# Connectors.net
KiCad netlist of a schematic drawn in Altium Designer
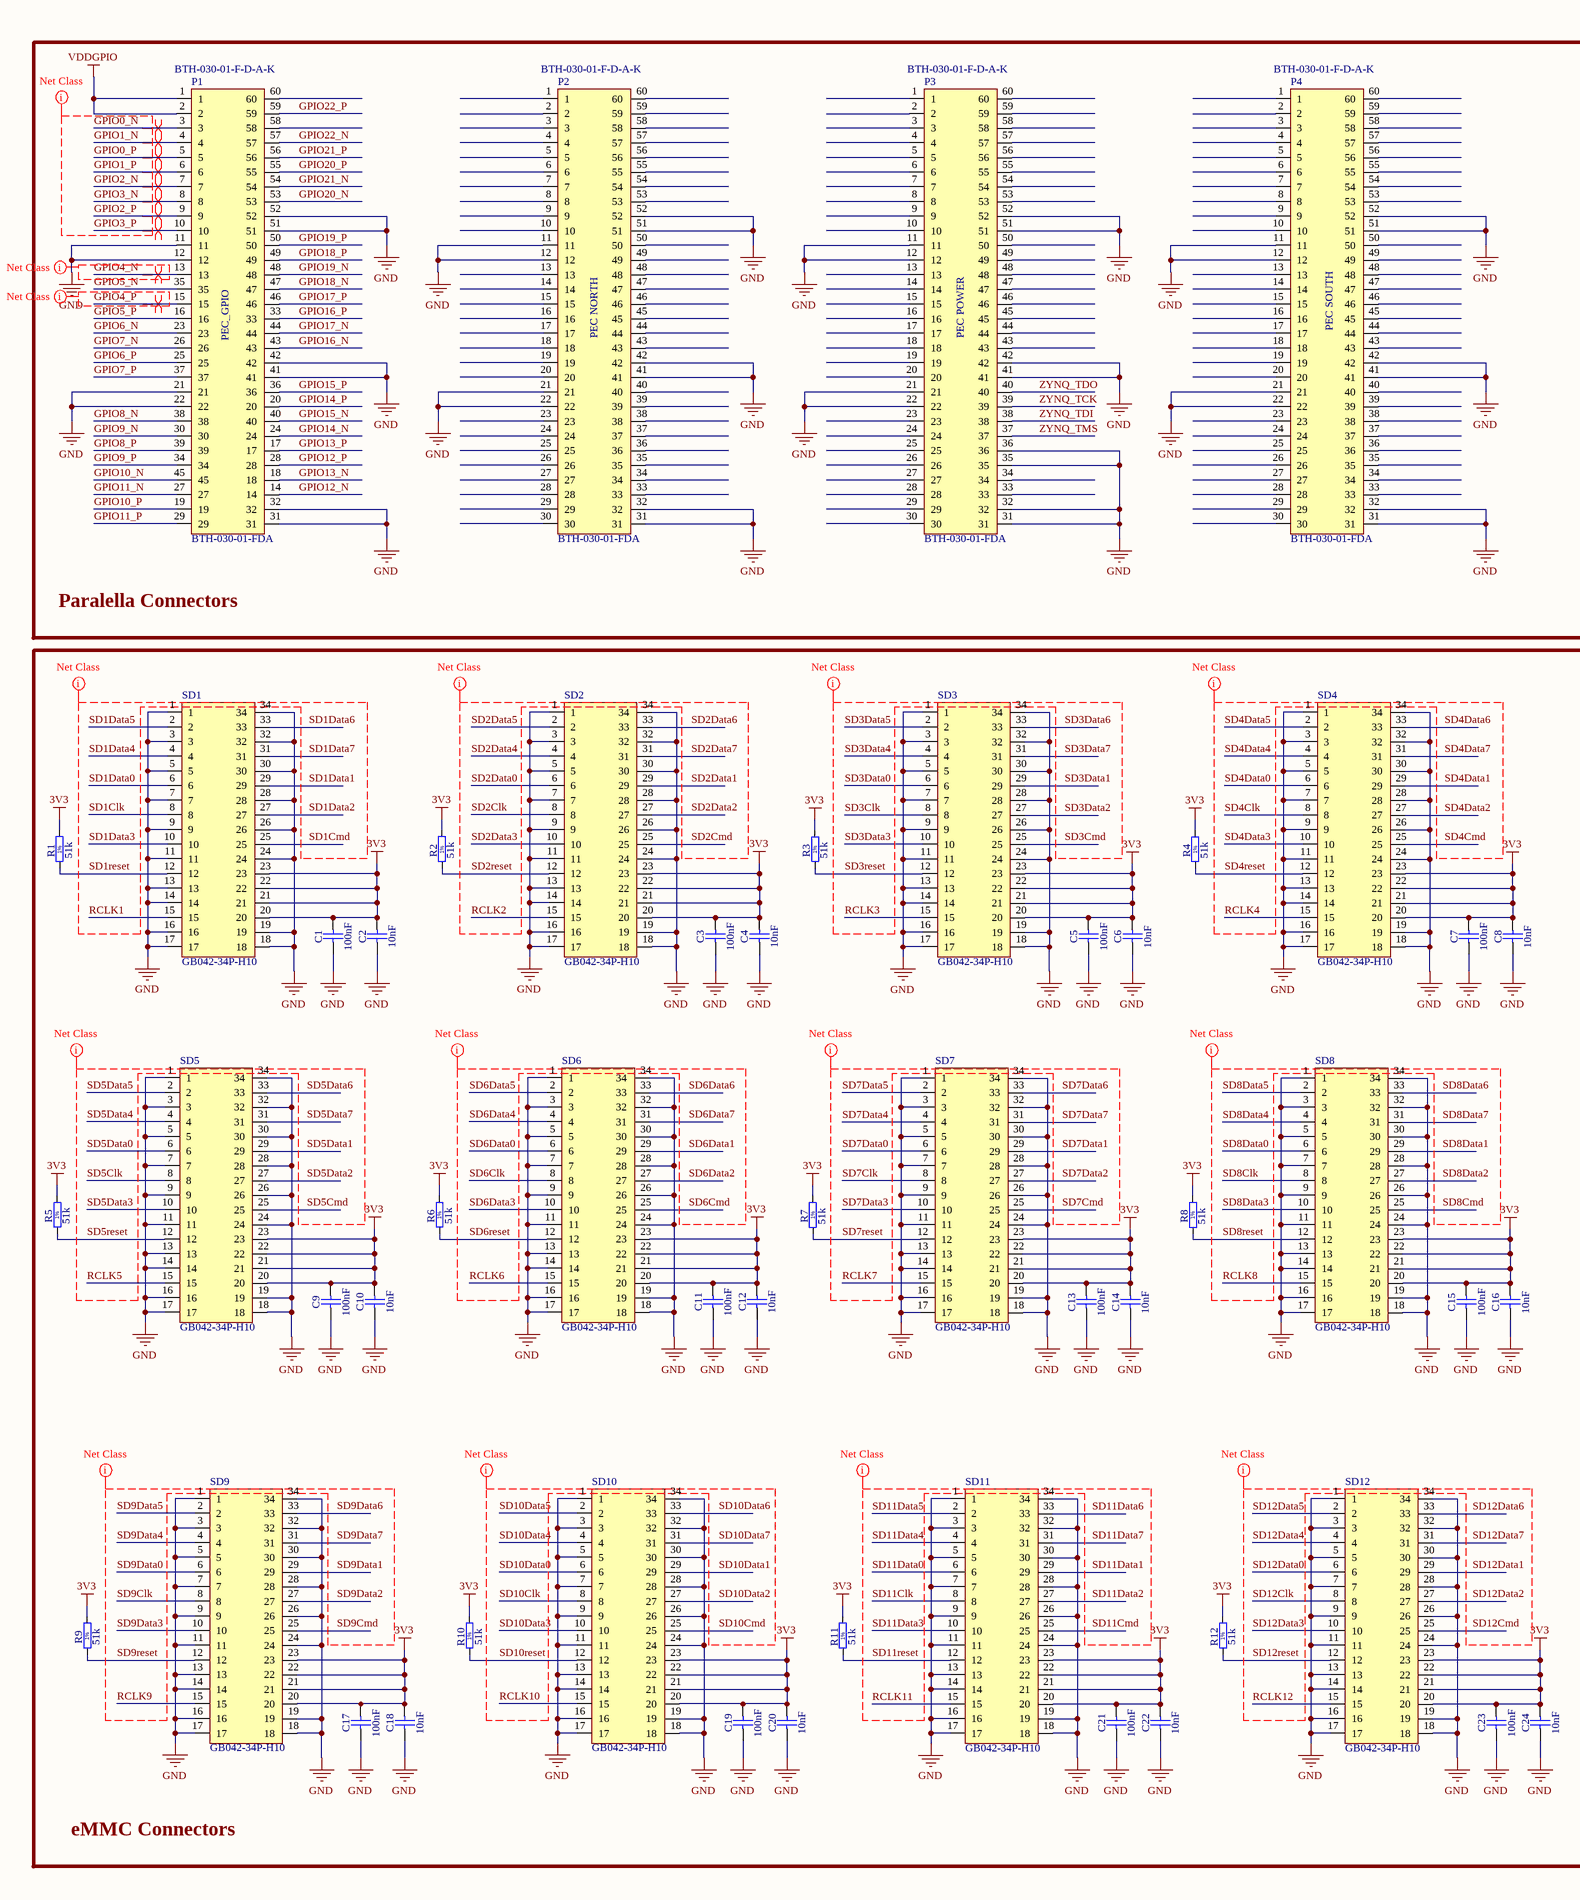
[diagram p0: Connectors.SchDoc, left]
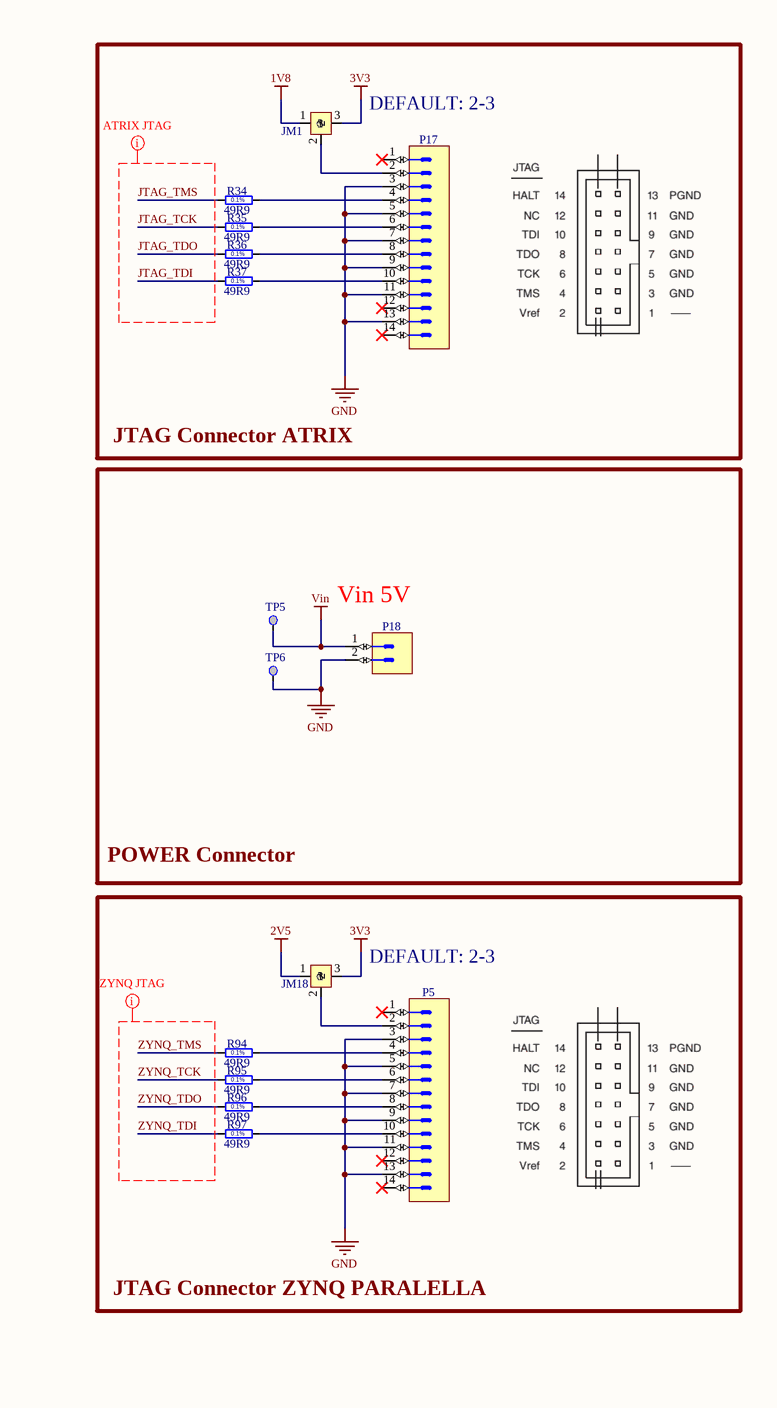
[diagram p1: Connectors.SchDoc, right]

(export (version "E")
  (design (tool "Eeschema 10.0.6"))
  (components
    (comp (ref "C1")
      (value "100nF")
      (footprint "CAPC1608X87N")
      (description "Non-polarised capacitor")
      (fields
        (field (name "PART NUMBER") "CC0603_100NF_50V_10%_X7R")
        (field (name "VOLTAGE") "50V")
        (field (name "AUTHOR") "CERN DEM JLC")
      )
      (libsource (lib "Capacitors") (part "Capacitor - non polarized"))
    )
    (comp (ref "C2")
      (value "10nF")
      (footprint "CAPC1608X87N")
      (description "Non-polarised capacitor")
      (fields
        (field (name "PART NUMBER") "CC0603_10NF_50V_10%_X7R")
        (field (name "VOLTAGE") "50V")
        (field (name "AUTHOR") "CERN DEM JLC")
      )
      (libsource (lib "Capacitors") (part "Capacitor - non polarized"))
    )
    (comp (ref "C3")
      (value "100nF")
      (footprint "CAPC1608X87N")
      (description "Non-polarised capacitor")
      (fields
        (field (name "PART NUMBER") "CC0603_100NF_50V_10%_X7R")
        (field (name "VOLTAGE") "50V")
        (field (name "AUTHOR") "CERN DEM JLC")
      )
      (libsource (lib "Capacitors") (part "Capacitor - non polarized"))
    )
    (comp (ref "C4")
      (value "10nF")
      (footprint "CAPC1608X87N")
      (description "Non-polarised capacitor")
      (fields
        (field (name "PART NUMBER") "CC0603_10NF_50V_10%_X7R")
        (field (name "VOLTAGE") "50V")
        (field (name "AUTHOR") "CERN DEM JLC")
      )
      (libsource (lib "Capacitors") (part "Capacitor - non polarized"))
    )
    (comp (ref "C5")
      (value "100nF")
      (footprint "CAPC1608X87N")
      (description "Non-polarised capacitor")
      (fields
        (field (name "PART NUMBER") "CC0603_100NF_50V_10%_X7R")
        (field (name "VOLTAGE") "50V")
        (field (name "AUTHOR") "CERN DEM JLC")
      )
      (libsource (lib "Capacitors") (part "Capacitor - non polarized"))
    )
    (comp (ref "C6")
      (value "10nF")
      (footprint "CAPC1608X87N")
      (description "Non-polarised capacitor")
      (fields
        (field (name "PART NUMBER") "CC0603_10NF_50V_10%_X7R")
        (field (name "VOLTAGE") "50V")
        (field (name "AUTHOR") "CERN DEM JLC")
      )
      (libsource (lib "Capacitors") (part "Capacitor - non polarized"))
    )
    (comp (ref "C7")
      (value "100nF")
      (footprint "CAPC1608X87N")
      (description "Non-polarised capacitor")
      (fields
        (field (name "PART NUMBER") "CC0603_100NF_50V_10%_X7R")
        (field (name "VOLTAGE") "50V")
        (field (name "AUTHOR") "CERN DEM JLC")
      )
      (libsource (lib "Capacitors") (part "Capacitor - non polarized"))
    )
    (comp (ref "C8")
      (value "10nF")
      (footprint "CAPC1608X87N")
      (description "Non-polarised capacitor")
      (fields
        (field (name "PART NUMBER") "CC0603_10NF_50V_10%_X7R")
        (field (name "VOLTAGE") "50V")
        (field (name "AUTHOR") "CERN DEM JLC")
      )
      (libsource (lib "Capacitors") (part "Capacitor - non polarized"))
    )
    (comp (ref "C9")
      (value "100nF")
      (footprint "CAPC1608X87N")
      (description "Non-polarised capacitor")
      (fields
        (field (name "PART NUMBER") "CC0603_100NF_50V_10%_X7R")
        (field (name "VOLTAGE") "50V")
        (field (name "AUTHOR") "CERN DEM JLC")
      )
      (libsource (lib "Capacitors") (part "Capacitor - non polarized"))
    )
    (comp (ref "C10")
      (value "10nF")
      (footprint "CAPC1608X87N")
      (description "Non-polarised capacitor")
      (fields
        (field (name "PART NUMBER") "CC0603_10NF_50V_10%_X7R")
        (field (name "VOLTAGE") "50V")
        (field (name "AUTHOR") "CERN DEM JLC")
      )
      (libsource (lib "Capacitors") (part "Capacitor - non polarized"))
    )
    (comp (ref "C11")
      (value "100nF")
      (footprint "CAPC1608X87N")
      (description "Non-polarised capacitor")
      (fields
        (field (name "PART NUMBER") "CC0603_100NF_50V_10%_X7R")
        (field (name "VOLTAGE") "50V")
        (field (name "AUTHOR") "CERN DEM JLC")
      )
      (libsource (lib "Capacitors") (part "Capacitor - non polarized"))
    )
    (comp (ref "C12")
      (value "10nF")
      (footprint "CAPC1608X87N")
      (description "Non-polarised capacitor")
      (fields
        (field (name "PART NUMBER") "CC0603_10NF_50V_10%_X7R")
        (field (name "VOLTAGE") "50V")
        (field (name "AUTHOR") "CERN DEM JLC")
      )
      (libsource (lib "Capacitors") (part "Capacitor - non polarized"))
    )
    (comp (ref "C13")
      (value "100nF")
      (footprint "CAPC1608X87N")
      (description "Non-polarised capacitor")
      (fields
        (field (name "PART NUMBER") "CC0603_100NF_50V_10%_X7R")
        (field (name "VOLTAGE") "50V")
        (field (name "AUTHOR") "CERN DEM JLC")
      )
      (libsource (lib "Capacitors") (part "Capacitor - non polarized"))
    )
    (comp (ref "C14")
      (value "10nF")
      (footprint "CAPC1608X87N")
      (description "Non-polarised capacitor")
      (fields
        (field (name "PART NUMBER") "CC0603_10NF_50V_10%_X7R")
        (field (name "VOLTAGE") "50V")
        (field (name "AUTHOR") "CERN DEM JLC")
      )
      (libsource (lib "Capacitors") (part "Capacitor - non polarized"))
    )
    (comp (ref "C15")
      (value "100nF")
      (footprint "CAPC1608X87N")
      (description "Non-polarised capacitor")
      (fields
        (field (name "PART NUMBER") "CC0603_100NF_50V_10%_X7R")
        (field (name "VOLTAGE") "50V")
        (field (name "AUTHOR") "CERN DEM JLC")
      )
      (libsource (lib "Capacitors") (part "Capacitor - non polarized"))
    )
    (comp (ref "C16")
      (value "10nF")
      (footprint "CAPC1608X87N")
      (description "Non-polarised capacitor")
      (fields
        (field (name "PART NUMBER") "CC0603_10NF_50V_10%_X7R")
        (field (name "VOLTAGE") "50V")
        (field (name "AUTHOR") "CERN DEM JLC")
      )
      (libsource (lib "Capacitors") (part "Capacitor - non polarized"))
    )
    (comp (ref "C17")
      (value "100nF")
      (footprint "CAPC1608X87N")
      (description "Non-polarised capacitor")
      (fields
        (field (name "PART NUMBER") "CC0603_100NF_50V_10%_X7R")
        (field (name "VOLTAGE") "50V")
        (field (name "AUTHOR") "CERN DEM JLC")
      )
      (libsource (lib "Capacitors") (part "Capacitor - non polarized"))
    )
    (comp (ref "C18")
      (value "10nF")
      (footprint "CAPC1608X87N")
      (description "Non-polarised capacitor")
      (fields
        (field (name "PART NUMBER") "CC0603_10NF_50V_10%_X7R")
        (field (name "VOLTAGE") "50V")
        (field (name "AUTHOR") "CERN DEM JLC")
      )
      (libsource (lib "Capacitors") (part "Capacitor - non polarized"))
    )
    (comp (ref "C19")
      (value "100nF")
      (footprint "CAPC1608X87N")
      (description "Non-polarised capacitor")
      (fields
        (field (name "PART NUMBER") "CC0603_100NF_50V_10%_X7R")
        (field (name "VOLTAGE") "50V")
        (field (name "AUTHOR") "CERN DEM JLC")
      )
      (libsource (lib "Capacitors") (part "Capacitor - non polarized"))
    )
    (comp (ref "C20")
      (value "10nF")
      (footprint "CAPC1608X87N")
      (description "Non-polarised capacitor")
      (fields
        (field (name "PART NUMBER") "CC0603_10NF_50V_10%_X7R")
        (field (name "VOLTAGE") "50V")
        (field (name "AUTHOR") "CERN DEM JLC")
      )
      (libsource (lib "Capacitors") (part "Capacitor - non polarized"))
    )
    (comp (ref "C21")
      (value "100nF")
      (footprint "CAPC1608X87N")
      (description "Non-polarised capacitor")
      (fields
        (field (name "PART NUMBER") "CC0603_100NF_50V_10%_X7R")
        (field (name "VOLTAGE") "50V")
        (field (name "AUTHOR") "CERN DEM JLC")
      )
      (libsource (lib "Capacitors") (part "Capacitor - non polarized"))
    )
    (comp (ref "C22")
      (value "10nF")
      (footprint "CAPC1608X87N")
      (description "Non-polarised capacitor")
      (fields
        (field (name "PART NUMBER") "CC0603_10NF_50V_10%_X7R")
        (field (name "VOLTAGE") "50V")
        (field (name "AUTHOR") "CERN DEM JLC")
      )
      (libsource (lib "Capacitors") (part "Capacitor - non polarized"))
    )
    (comp (ref "C23")
      (value "100nF")
      (footprint "CAPC1608X87N")
      (description "Non-polarised capacitor")
      (fields
        (field (name "PART NUMBER") "CC0603_100NF_50V_10%_X7R")
        (field (name "VOLTAGE") "50V")
        (field (name "AUTHOR") "CERN DEM JLC")
      )
      (libsource (lib "Capacitors") (part "Capacitor - non polarized"))
    )
    (comp (ref "C24")
      (value "10nF")
      (footprint "CAPC1608X87N")
      (description "Non-polarised capacitor")
      (fields
        (field (name "PART NUMBER") "CC0603_10NF_50V_10%_X7R")
        (field (name "VOLTAGE") "50V")
        (field (name "AUTHOR") "CERN DEM JLC")
      )
      (libsource (lib "Capacitors") (part "Capacitor - non polarized"))
    )
    (comp (ref "JM1")
      (value "Jumper 0R")
      (footprint "JUMPER_0R")
      (libsource (lib "SCHLIB") (part "Jumper 0R"))
    )
    (comp (ref "JM18")
      (value "Jumper 0R")
      (footprint "JUMPER_0R")
      (libsource (lib "SCHLIB") (part "Jumper 0R"))
    )
    (comp (ref "P1")
      (value "BTH-030-01-FDA")
      (footprint "BTH-030-01-F-D-A")
      (description "Conn Micro Terminal HDR 60 POS 0.5mm Solder ST SMD")
      (fields
        (field (name "MANUFACTURER") "Samtec")
        (field (name "MANUFACTURER PART NUMBER") "BTH-030-01-F-D-A-K")
      )
      (libsource (lib "") (part "BTH-030-01-FDA_1"))
    )
    (comp (ref "P2")
      (value "BTH-030-01-FDA")
      (footprint "BTH-030-01-F-D-A")
      (description "Conn Micro Terminal HDR 60 POS 0.5mm Solder ST SMD")
      (fields
        (field (name "MANUFACTURER") "Samtec")
        (field (name "MANUFACTURER PART NUMBER") "BTH-030-01-F-D-A-K")
      )
      (libsource (lib "SCHLIB") (part "BTH-030-01-FDA"))
    )
    (comp (ref "P3")
      (value "BTH-030-01-FDA")
      (footprint "BTH-030-01-F-D-A")
      (description "Conn Micro Terminal HDR 60 POS 0.5mm Solder ST SMD")
      (fields
        (field (name "MANUFACTURER") "Samtec")
        (field (name "MANUFACTURER PART NUMBER") "BTH-030-01-F-D-A-K")
      )
      (libsource (lib "SCHLIB") (part "BTH-030-01-FDA"))
    )
    (comp (ref "P4")
      (value "BTH-030-01-FDA")
      (footprint "BTH-030-01-F-D-A")
      (description "Conn Micro Terminal HDR 60 POS 0.5mm Solder ST SMD")
      (fields
        (field (name "MANUFACTURER") "Samtec")
        (field (name "MANUFACTURER PART NUMBER") "BTH-030-01-F-D-A-K")
      )
      (libsource (lib "SCHLIB") (part "BTH-030-01-FDA"))
    )
    (comp (ref "P5")
      (value "~")
      (footprint "MOLEX_87832-1420")
      (description "Connector 14 Male")
      (fields
        (field (name "MANUFACTURER PART NUMBER") "0878321420")
        (field (name "MANUFACTURER") "Molex, LLC")
      )
      (libsource (lib "SCHLIB") (part "Connector 14 Male"))
    )
    (comp (ref "P17")
      (value "~")
      (footprint "MOLEX_87832-1420")
      (description "Connector 14 Male")
      (fields
        (field (name "MANUFACTURER PART NUMBER") "0878321420")
        (field (name "MANUFACTURER") "Molex, LLC")
      )
      (libsource (lib "SCHLIB") (part "Connector 14 Male"))
    )
    (comp (ref "P18")
      (value "KK®")
      (footprint "MOLEX_26-60-4020")
      (description "Connector 2 Male")
      (fields
        (field (name "PART NUMBER") "MOLEX_26-60-4020")
        (field (name "MANUFACTURER") "Molex, LLC")
        (field (name "AUTHOR") "CERN DEM JLC")
      )
      (libsource (lib "Connectors") (part "Connector 2 Male"))
    )
    (comp (ref "R1")
      (value "51k")
      (footprint "RESC1608X55N")
      (description "Resistor - 1%")
      (fields
        (field (name "PART NUMBER") "R0603_51K_1%_0.1W_100PPM")
        (field (name "POWER") "0.1W")
        (field (name "AUTHOR") "CERN DEM JLC")
      )
      (libsource (lib "Resistors") (part "Resistor - 1%"))
    )
    (comp (ref "R2")
      (value "51k")
      (footprint "RESC1608X55N")
      (description "Resistor - 1%")
      (fields
        (field (name "PART NUMBER") "R0603_51K_1%_0.1W_100PPM")
        (field (name "POWER") "0.1W")
        (field (name "AUTHOR") "CERN DEM JLC")
      )
      (libsource (lib "Resistors") (part "Resistor - 1%"))
    )
    (comp (ref "R3")
      (value "51k")
      (footprint "RESC1608X55N")
      (description "Resistor - 1%")
      (fields
        (field (name "PART NUMBER") "R0603_51K_1%_0.1W_100PPM")
        (field (name "POWER") "0.1W")
        (field (name "AUTHOR") "CERN DEM JLC")
      )
      (libsource (lib "Resistors") (part "Resistor - 1%"))
    )
    (comp (ref "R4")
      (value "51k")
      (footprint "RESC1608X55N")
      (description "Resistor - 1%")
      (fields
        (field (name "PART NUMBER") "R0603_51K_1%_0.1W_100PPM")
        (field (name "POWER") "0.1W")
        (field (name "AUTHOR") "CERN DEM JLC")
      )
      (libsource (lib "Resistors") (part "Resistor - 1%"))
    )
    (comp (ref "R5")
      (value "51k")
      (footprint "RESC1608X55N")
      (description "Resistor - 1%")
      (fields
        (field (name "PART NUMBER") "R0603_51K_1%_0.1W_100PPM")
        (field (name "POWER") "0.1W")
        (field (name "AUTHOR") "CERN DEM JLC")
      )
      (libsource (lib "Resistors") (part "Resistor - 1%"))
    )
    (comp (ref "R6")
      (value "51k")
      (footprint "RESC1608X55N")
      (description "Resistor - 1%")
      (fields
        (field (name "PART NUMBER") "R0603_51K_1%_0.1W_100PPM")
        (field (name "POWER") "0.1W")
        (field (name "AUTHOR") "CERN DEM JLC")
      )
      (libsource (lib "Resistors") (part "Resistor - 1%"))
    )
    (comp (ref "R7")
      (value "51k")
      (footprint "RESC1608X55N")
      (description "Resistor - 1%")
      (fields
        (field (name "PART NUMBER") "R0603_51K_1%_0.1W_100PPM")
        (field (name "POWER") "0.1W")
        (field (name "AUTHOR") "CERN DEM JLC")
      )
      (libsource (lib "Resistors") (part "Resistor - 1%"))
    )
    (comp (ref "R8")
      (value "51k")
      (footprint "RESC1608X55N")
      (description "Resistor - 1%")
      (fields
        (field (name "PART NUMBER") "R0603_51K_1%_0.1W_100PPM")
        (field (name "POWER") "0.1W")
        (field (name "AUTHOR") "CERN DEM JLC")
      )
      (libsource (lib "Resistors") (part "Resistor - 1%"))
    )
    (comp (ref "R9")
      (value "51k")
      (footprint "RESC1608X55N")
      (description "Resistor - 1%")
      (fields
        (field (name "PART NUMBER") "R0603_51K_1%_0.1W_100PPM")
        (field (name "POWER") "0.1W")
        (field (name "AUTHOR") "CERN DEM JLC")
      )
      (libsource (lib "Resistors") (part "Resistor - 1%"))
    )
    (comp (ref "R10")
      (value "51k")
      (footprint "RESC1608X55N")
      (description "Resistor - 1%")
      (fields
        (field (name "PART NUMBER") "R0603_51K_1%_0.1W_100PPM")
        (field (name "POWER") "0.1W")
        (field (name "AUTHOR") "CERN DEM JLC")
      )
      (libsource (lib "Resistors") (part "Resistor - 1%"))
    )
    (comp (ref "R11")
      (value "51k")
      (footprint "RESC1608X55N")
      (description "Resistor - 1%")
      (fields
        (field (name "PART NUMBER") "R0603_51K_1%_0.1W_100PPM")
        (field (name "POWER") "0.1W")
        (field (name "AUTHOR") "CERN DEM JLC")
      )
      (libsource (lib "Resistors") (part "Resistor - 1%"))
    )
    (comp (ref "R12")
      (value "51k")
      (footprint "RESC1608X55N")
      (description "Resistor - 1%")
      (fields
        (field (name "PART NUMBER") "R0603_51K_1%_0.1W_100PPM")
        (field (name "POWER") "0.1W")
        (field (name "AUTHOR") "CERN DEM JLC")
      )
      (libsource (lib "Resistors") (part "Resistor - 1%"))
    )
    (comp (ref "R34")
      (value "49R9")
      (footprint "RESC1608X55N")
      (description "Resistor - 0.1%")
      (fields
        (field (name "PART NUMBER") "R0603_49R9_0.1%_0.063W_10PPM")
        (field (name "POWER") "0.063W")
        (field (name "AUTHOR") "CERN DEM JLC")
      )
      (libsource (lib "Resistors") (part "Resistor - 0.1%"))
    )
    (comp (ref "R35")
      (value "49R9")
      (footprint "RESC1608X55N")
      (description "Resistor - 0.1%")
      (fields
        (field (name "PART NUMBER") "R0603_49R9_0.1%_0.063W_10PPM")
        (field (name "POWER") "0.063W")
        (field (name "AUTHOR") "CERN DEM JLC")
      )
      (libsource (lib "Resistors") (part "Resistor - 0.1%"))
    )
    (comp (ref "R36")
      (value "49R9")
      (footprint "RESC1608X55N")
      (description "Resistor - 0.1%")
      (fields
        (field (name "PART NUMBER") "R0603_49R9_0.1%_0.063W_10PPM")
        (field (name "POWER") "0.063W")
        (field (name "AUTHOR") "CERN DEM JLC")
      )
      (libsource (lib "Resistors") (part "Resistor - 0.1%"))
    )
    (comp (ref "R37")
      (value "49R9")
      (footprint "RESC1608X55N")
      (description "Resistor - 0.1%")
      (fields
        (field (name "PART NUMBER") "R0603_49R9_0.1%_0.063W_10PPM")
        (field (name "POWER") "0.063W")
        (field (name "AUTHOR") "CERN DEM JLC")
      )
      (libsource (lib "Resistors") (part "Resistor - 0.1%"))
    )
    (comp (ref "R94")
      (value "49R9")
      (footprint "RESC1608X55N")
      (description "Resistor - 0.1%")
      (fields
        (field (name "PART NUMBER") "R0603_49R9_0.1%_0.063W_10PPM")
        (field (name "POWER") "0.063W")
        (field (name "AUTHOR") "CERN DEM JLC")
      )
      (libsource (lib "Resistors") (part "Resistor - 0.1%"))
    )
    (comp (ref "R95")
      (value "49R9")
      (footprint "RESC1608X55N")
      (description "Resistor - 0.1%")
      (fields
        (field (name "PART NUMBER") "R0603_49R9_0.1%_0.063W_10PPM")
        (field (name "POWER") "0.063W")
        (field (name "AUTHOR") "CERN DEM JLC")
      )
      (libsource (lib "Resistors") (part "Resistor - 0.1%"))
    )
    (comp (ref "R96")
      (value "49R9")
      (footprint "RESC1608X55N")
      (description "Resistor - 0.1%")
      (fields
        (field (name "PART NUMBER") "R0603_49R9_0.1%_0.063W_10PPM")
        (field (name "POWER") "0.063W")
        (field (name "AUTHOR") "CERN DEM JLC")
      )
      (libsource (lib "Resistors") (part "Resistor - 0.1%"))
    )
    (comp (ref "R97")
      (value "49R9")
      (footprint "RESC1608X55N")
      (description "Resistor - 0.1%")
      (fields
        (field (name "PART NUMBER") "R0603_49R9_0.1%_0.063W_10PPM")
        (field (name "POWER") "0.063W")
        (field (name "AUTHOR") "CERN DEM JLC")
      )
      (libsource (lib "Resistors") (part "Resistor - 0.1%"))
    )
    (comp (ref "SD1")
      (value "GB042-34P-H10")
      (footprint "GB042-34P-H10")
      (description "Connector, eMMC")
      (libsource (lib "SCHLIB") (part "GB042-34P-H10"))
    )
    (comp (ref "SD2")
      (value "GB042-34P-H10")
      (footprint "GB042-34P-H10")
      (description "Connector, eMMC")
      (libsource (lib "SCHLIB") (part "GB042-34P-H10"))
    )
    (comp (ref "SD3")
      (value "GB042-34P-H10")
      (footprint "GB042-34P-H10")
      (description "Connector, eMMC")
      (libsource (lib "SCHLIB") (part "GB042-34P-H10"))
    )
    (comp (ref "SD4")
      (value "GB042-34P-H10")
      (footprint "GB042-34P-H10")
      (description "Connector, eMMC")
      (libsource (lib "SCHLIB") (part "GB042-34P-H10"))
    )
    (comp (ref "SD5")
      (value "GB042-34P-H10")
      (footprint "GB042-34P-H10")
      (description "Connector, eMMC")
      (libsource (lib "SCHLIB") (part "GB042-34P-H10"))
    )
    (comp (ref "SD6")
      (value "GB042-34P-H10")
      (footprint "GB042-34P-H10")
      (description "Connector, eMMC")
      (libsource (lib "SCHLIB") (part "GB042-34P-H10"))
    )
    (comp (ref "SD7")
      (value "GB042-34P-H10")
      (footprint "GB042-34P-H10")
      (description "Connector, eMMC")
      (libsource (lib "SCHLIB") (part "GB042-34P-H10"))
    )
    (comp (ref "SD8")
      (value "GB042-34P-H10")
      (footprint "GB042-34P-H10")
      (description "Connector, eMMC")
      (libsource (lib "SCHLIB") (part "GB042-34P-H10"))
    )
    (comp (ref "SD9")
      (value "GB042-34P-H10")
      (footprint "GB042-34P-H10")
      (description "Connector, eMMC")
      (libsource (lib "SCHLIB") (part "GB042-34P-H10"))
    )
    (comp (ref "SD10")
      (value "GB042-34P-H10")
      (footprint "GB042-34P-H10")
      (description "Connector, eMMC")
      (libsource (lib "SCHLIB") (part "GB042-34P-H10"))
    )
    (comp (ref "SD11")
      (value "GB042-34P-H10")
      (footprint "GB042-34P-H10")
      (description "Connector, eMMC")
      (libsource (lib "SCHLIB") (part "GB042-34P-H10"))
    )
    (comp (ref "SD12")
      (value "GB042-34P-H10")
      (footprint "GB042-34P-H10")
      (description "Connector, eMMC")
      (libsource (lib "SCHLIB") (part "GB042-34P-H10"))
    )
    (comp (ref "TP5")
      (value "TP")
      (footprint "TP")
      (description "Test Point")
      (libsource (lib "SCHLIB") (part "Test Point"))
    )
    (comp (ref "TP6")
      (value "TP")
      (footprint "TP")
      (description "Test Point")
      (libsource (lib "SCHLIB") (part "Test Point"))
    )
  )
  (nets
    (net (code "1") (name "/GPIO0_N") (class "Default")
      (node (ref "P1") (pin "3") (pinfunction "3_3") (pintype "passive"))
    )
    (net (code "2") (name "/GPIO0_P") (class "Default")
      (node (ref "P1") (pin "5") (pinfunction "5_5") (pintype "passive"))
    )
    (net (code "3") (name "/GPIO1_N") (class "Default")
      (node (ref "P1") (pin "4") (pinfunction "4_4") (pintype "passive"))
    )
    (net (code "4") (name "/GPIO1_P") (class "Default")
      (node (ref "P1") (pin "6") (pinfunction "6_6") (pintype "passive"))
    )
    (net (code "5") (name "/GPIO2_N") (class "Default")
      (node (ref "P1") (pin "7") (pinfunction "7_7") (pintype "passive"))
    )
    (net (code "6") (name "/GPIO2_P") (class "Default")
      (node (ref "P1") (pin "9") (pinfunction "9_9") (pintype "passive"))
    )
    (net (code "7") (name "/GPIO3_N") (class "Default")
      (node (ref "P1") (pin "8") (pinfunction "8_8") (pintype "passive"))
    )
    (net (code "8") (name "/GPIO3_P") (class "Default")
      (node (ref "P1") (pin "10") (pinfunction "10_10") (pintype "passive"))
    )
    (net (code "9") (name "/GPIO4_N") (class "Default")
      (node (ref "P1") (pin "13") (pinfunction "13_13") (pintype "passive"))
    )
    (net (code "10") (name "/GPIO4_P") (class "Default")
      (node (ref "P1") (pin "15") (pinfunction "15_15") (pintype "passive"))
    )
    (net (code "11") (name "/GPIO5_N") (class "Default")
      (node (ref "P1") (pin "35") (pinfunction "35_35") (pintype "passive"))
    )
    (net (code "12") (name "/GPIO5_P") (class "Default")
      (node (ref "P1") (pin "16") (pinfunction "16_16") (pintype "passive"))
    )
    (net (code "13") (name "/GPIO6_N") (class "Default")
      (node (ref "P1") (pin "23") (pinfunction "23_23") (pintype "passive"))
    )
    (net (code "14") (name "/GPIO6_P") (class "Default")
      (node (ref "P1") (pin "25") (pinfunction "25_25") (pintype "passive"))
    )
    (net (code "15") (name "/GPIO7_N") (class "Default")
      (node (ref "P1") (pin "26") (pinfunction "26_26") (pintype "passive"))
    )
    (net (code "16") (name "/GPIO7_P") (class "Default")
      (node (ref "P1") (pin "37") (pinfunction "37_37") (pintype "passive"))
    )
    (net (code "17") (name "/GPIO8_N") (class "Default")
      (node (ref "P1") (pin "38") (pinfunction "38_38") (pintype "passive"))
    )
    (net (code "18") (name "/GPIO8_P") (class "Default")
      (node (ref "P1") (pin "39") (pinfunction "39_39") (pintype "passive"))
    )
    (net (code "19") (name "/GPIO9_N") (class "Default")
      (node (ref "P1") (pin "30") (pinfunction "30_30") (pintype "passive"))
    )
    (net (code "20") (name "/GPIO9_P") (class "Default")
      (node (ref "P1") (pin "34") (pinfunction "34_34") (pintype "passive"))
    )
    (net (code "21") (name "/GPIO10_N") (class "Default")
      (node (ref "P1") (pin "45") (pinfunction "45_45") (pintype "passive"))
    )
    (net (code "22") (name "/GPIO10_P") (class "Default")
      (node (ref "P1") (pin "19") (pinfunction "19_19") (pintype "passive"))
    )
    (net (code "23") (name "/GPIO11_N") (class "Default")
      (node (ref "P1") (pin "27") (pinfunction "27_27") (pintype "passive"))
    )
    (net (code "24") (name "/GPIO11_P") (class "Default")
      (node (ref "P1") (pin "29") (pinfunction "29_29") (pintype "passive"))
    )
    (net (code "25") (name "/GPIO12_N") (class "Default")
      (node (ref "P1") (pin "14") (pinfunction "14_14") (pintype "passive"))
    )
    (net (code "26") (name "/GPIO12_P") (class "Default")
      (node (ref "P1") (pin "28") (pinfunction "28_28") (pintype "passive"))
    )
    (net (code "27") (name "/GPIO13_N") (class "Default")
      (node (ref "P1") (pin "18") (pinfunction "18_18") (pintype "passive"))
    )
    (net (code "28") (name "/GPIO13_P") (class "Default")
      (node (ref "P1") (pin "17") (pinfunction "17_17") (pintype "passive"))
    )
    (net (code "29") (name "/GPIO14_N") (class "Default")
      (node (ref "P1") (pin "24") (pinfunction "24_24") (pintype "passive"))
    )
    (net (code "30") (name "/GPIO14_P") (class "Default")
      (node (ref "P1") (pin "20") (pinfunction "20_20") (pintype "passive"))
    )
    (net (code "31") (name "/GPIO15_N") (class "Default")
      (node (ref "P1") (pin "40") (pinfunction "40_40") (pintype "passive"))
    )
    (net (code "32") (name "/GPIO15_P") (class "Default")
      (node (ref "P1") (pin "36") (pinfunction "36_36") (pintype "passive"))
    )
    (net (code "33") (name "/GPIO16_N") (class "Default")
      (node (ref "P1") (pin "43") (pinfunction "43_43") (pintype "passive"))
    )
    (net (code "34") (name "/GPIO16_P") (class "Default")
      (node (ref "P1") (pin "33") (pinfunction "33_33") (pintype "passive"))
    )
    (net (code "35") (name "/GPIO17_N") (class "Default")
      (node (ref "P1") (pin "44") (pinfunction "44_44") (pintype "passive"))
    )
    (net (code "36") (name "/GPIO17_P") (class "Default")
      (node (ref "P1") (pin "46") (pinfunction "46_46") (pintype "passive"))
    )
    (net (code "37") (name "/GPIO18_N") (class "Default")
      (node (ref "P1") (pin "47") (pinfunction "47_47") (pintype "passive"))
    )
    (net (code "38") (name "/GPIO18_P") (class "Default")
      (node (ref "P1") (pin "49") (pinfunction "49_49") (pintype "passive"))
    )
    (net (code "39") (name "/GPIO19_N") (class "Default")
      (node (ref "P1") (pin "48") (pinfunction "48_48") (pintype "passive"))
    )
    (net (code "40") (name "/GPIO19_P") (class "Default")
      (node (ref "P1") (pin "50") (pinfunction "50_50") (pintype "passive"))
    )
    (net (code "41") (name "/GPIO20_N") (class "Default")
      (node (ref "P1") (pin "53") (pinfunction "53_53") (pintype "passive"))
    )
    (net (code "42") (name "/GPIO20_P") (class "Default")
      (node (ref "P1") (pin "55") (pinfunction "55_55") (pintype "passive"))
    )
    (net (code "43") (name "/GPIO21_N") (class "Default")
      (node (ref "P1") (pin "54") (pinfunction "54_54") (pintype "passive"))
    )
    (net (code "44") (name "/GPIO21_P") (class "Default")
      (node (ref "P1") (pin "56") (pinfunction "56_56") (pintype "passive"))
    )
    (net (code "45") (name "/GPIO22_N") (class "Default")
      (node (ref "P1") (pin "57") (pinfunction "57_57") (pintype "passive"))
    )
    (net (code "46") (name "/GPIO22_P") (class "Default")
      (node (ref "P1") (pin "59") (pinfunction "59_59") (pintype "passive"))
    )
    (net (code "47") (name "/JTAG_TCK") (class "Default")
      (node (ref "R35") (pin "1") (pinfunction "1_1") (pintype "passive"))
    )
    (net (code "48") (name "/JTAG_TDI") (class "Default")
      (node (ref "R37") (pin "1") (pinfunction "1_1") (pintype "passive"))
    )
    (net (code "49") (name "/JTAG_TDO") (class "Default")
      (node (ref "R36") (pin "1") (pinfunction "1_1") (pintype "passive"))
    )
    (net (code "50") (name "/JTAG_TMS") (class "Default")
      (node (ref "R34") (pin "1") (pinfunction "1_1") (pintype "passive"))
    )
    (net (code "51") (name "/RCLK1") (class "Default")
      (node (ref "SD1") (pin "15") (pinfunction "15_15") (pintype "passive"))
    )
    (net (code "52") (name "/RCLK2") (class "Default")
      (node (ref "SD2") (pin "15") (pinfunction "15_15") (pintype "passive"))
    )
    (net (code "53") (name "/RCLK3") (class "Default")
      (node (ref "SD3") (pin "15") (pinfunction "15_15") (pintype "passive"))
    )
    (net (code "54") (name "/RCLK4") (class "Default")
      (node (ref "SD4") (pin "15") (pinfunction "15_15") (pintype "passive"))
    )
    (net (code "55") (name "/RCLK5") (class "Default")
      (node (ref "SD5") (pin "15") (pinfunction "15_15") (pintype "passive"))
    )
    (net (code "56") (name "/RCLK6") (class "Default")
      (node (ref "SD6") (pin "15") (pinfunction "15_15") (pintype "passive"))
    )
    (net (code "57") (name "/RCLK7") (class "Default")
      (node (ref "SD7") (pin "15") (pinfunction "15_15") (pintype "passive"))
    )
    (net (code "58") (name "/RCLK8") (class "Default")
      (node (ref "SD8") (pin "15") (pinfunction "15_15") (pintype "passive"))
    )
    (net (code "59") (name "/RCLK9") (class "Default")
      (node (ref "SD9") (pin "15") (pinfunction "15_15") (pintype "passive"))
    )
    (net (code "60") (name "/RCLK10") (class "Default")
      (node (ref "SD10") (pin "15") (pinfunction "15_15") (pintype "passive"))
    )
    (net (code "61") (name "/RCLK11") (class "Default")
      (node (ref "SD11") (pin "15") (pinfunction "15_15") (pintype "passive"))
    )
    (net (code "62") (name "/RCLK12") (class "Default")
      (node (ref "SD12") (pin "15") (pinfunction "15_15") (pintype "passive"))
    )
    (net (code "63") (name "/SD1Clk") (class "Default")
      (node (ref "SD1") (pin "8") (pinfunction "8_8") (pintype "passive"))
    )
    (net (code "64") (name "/SD1Cmd") (class "Default")
      (node (ref "SD1") (pin "25") (pinfunction "25_25") (pintype "passive"))
    )
    (net (code "65") (name "/SD1Data0") (class "Default")
      (node (ref "SD1") (pin "6") (pinfunction "6_6") (pintype "passive"))
    )
    (net (code "66") (name "/SD1Data1") (class "Default")
      (node (ref "SD1") (pin "29") (pinfunction "29_29") (pintype "passive"))
    )
    (net (code "67") (name "/SD1Data2") (class "Default")
      (node (ref "SD1") (pin "27") (pinfunction "27_27") (pintype "passive"))
    )
    (net (code "68") (name "/SD1Data3") (class "Default")
      (node (ref "SD1") (pin "10") (pinfunction "10_10") (pintype "passive"))
    )
    (net (code "69") (name "/SD1Data4") (class "Default")
      (node (ref "SD1") (pin "4") (pinfunction "4_4") (pintype "passive"))
    )
    (net (code "70") (name "/SD1Data5") (class "Default")
      (node (ref "SD1") (pin "2") (pinfunction "2_2") (pintype "passive"))
    )
    (net (code "71") (name "/SD1Data6") (class "Default")
      (node (ref "SD1") (pin "33") (pinfunction "33_33") (pintype "passive"))
    )
    (net (code "72") (name "/SD1Data7") (class "Default")
      (node (ref "SD1") (pin "31") (pinfunction "31_31") (pintype "passive"))
    )
    (net (code "73") (name "/SD1reset") (class "Default")
      (node (ref "R1") (pin "1") (pinfunction "1_1") (pintype "passive"))
      (node (ref "SD1") (pin "12") (pinfunction "12_12") (pintype "passive"))
    )
    (net (code "74") (name "/SD2Clk") (class "Default")
      (node (ref "SD2") (pin "8") (pinfunction "8_8") (pintype "passive"))
    )
    (net (code "75") (name "/SD2Cmd") (class "Default")
      (node (ref "SD2") (pin "25") (pinfunction "25_25") (pintype "passive"))
    )
    (net (code "76") (name "/SD2Data0") (class "Default")
      (node (ref "SD2") (pin "6") (pinfunction "6_6") (pintype "passive"))
    )
    (net (code "77") (name "/SD2Data1") (class "Default")
      (node (ref "SD2") (pin "29") (pinfunction "29_29") (pintype "passive"))
    )
    (net (code "78") (name "/SD2Data2") (class "Default")
      (node (ref "SD2") (pin "27") (pinfunction "27_27") (pintype "passive"))
    )
    (net (code "79") (name "/SD2Data3") (class "Default")
      (node (ref "SD2") (pin "10") (pinfunction "10_10") (pintype "passive"))
    )
    (net (code "80") (name "/SD2Data4") (class "Default")
      (node (ref "SD2") (pin "4") (pinfunction "4_4") (pintype "passive"))
    )
    (net (code "81") (name "/SD2Data5") (class "Default")
      (node (ref "SD2") (pin "2") (pinfunction "2_2") (pintype "passive"))
    )
    (net (code "82") (name "/SD2Data6") (class "Default")
      (node (ref "SD2") (pin "33") (pinfunction "33_33") (pintype "passive"))
    )
    (net (code "83") (name "/SD2Data7") (class "Default")
      (node (ref "SD2") (pin "31") (pinfunction "31_31") (pintype "passive"))
    )
    (net (code "84") (name "/SD2reset") (class "Default")
      (node (ref "R2") (pin "1") (pinfunction "1_1") (pintype "passive"))
      (node (ref "SD2") (pin "12") (pinfunction "12_12") (pintype "passive"))
    )
    (net (code "85") (name "/SD3Clk") (class "Default")
      (node (ref "SD3") (pin "8") (pinfunction "8_8") (pintype "passive"))
    )
    (net (code "86") (name "/SD3Cmd") (class "Default")
      (node (ref "SD3") (pin "25") (pinfunction "25_25") (pintype "passive"))
    )
    (net (code "87") (name "/SD3Data0") (class "Default")
      (node (ref "SD3") (pin "6") (pinfunction "6_6") (pintype "passive"))
    )
    (net (code "88") (name "/SD3Data1") (class "Default")
      (node (ref "SD3") (pin "29") (pinfunction "29_29") (pintype "passive"))
    )
    (net (code "89") (name "/SD3Data2") (class "Default")
      (node (ref "SD3") (pin "27") (pinfunction "27_27") (pintype "passive"))
    )
    (net (code "90") (name "/SD3Data3") (class "Default")
      (node (ref "SD3") (pin "10") (pinfunction "10_10") (pintype "passive"))
    )
    (net (code "91") (name "/SD3Data4") (class "Default")
      (node (ref "SD3") (pin "4") (pinfunction "4_4") (pintype "passive"))
    )
    (net (code "92") (name "/SD3Data5") (class "Default")
      (node (ref "SD3") (pin "2") (pinfunction "2_2") (pintype "passive"))
    )
    (net (code "93") (name "/SD3Data6") (class "Default")
      (node (ref "SD3") (pin "33") (pinfunction "33_33") (pintype "passive"))
    )
    (net (code "94") (name "/SD3Data7") (class "Default")
      (node (ref "SD3") (pin "31") (pinfunction "31_31") (pintype "passive"))
    )
    (net (code "95") (name "/SD3reset") (class "Default")
      (node (ref "R3") (pin "1") (pinfunction "1_1") (pintype "passive"))
      (node (ref "SD3") (pin "12") (pinfunction "12_12") (pintype "passive"))
    )
    (net (code "96") (name "/SD4Clk") (class "Default")
      (node (ref "SD4") (pin "8") (pinfunction "8_8") (pintype "passive"))
    )
    (net (code "97") (name "/SD4Cmd") (class "Default")
      (node (ref "SD4") (pin "25") (pinfunction "25_25") (pintype "passive"))
    )
    (net (code "98") (name "/SD4Data0") (class "Default")
      (node (ref "SD4") (pin "6") (pinfunction "6_6") (pintype "passive"))
    )
    (net (code "99") (name "/SD4Data1") (class "Default")
      (node (ref "SD4") (pin "29") (pinfunction "29_29") (pintype "passive"))
    )
    (net (code "100") (name "/SD4Data2") (class "Default")
      (node (ref "SD4") (pin "27") (pinfunction "27_27") (pintype "passive"))
    )
    (net (code "101") (name "/SD4Data3") (class "Default")
      (node (ref "SD4") (pin "10") (pinfunction "10_10") (pintype "passive"))
    )
    (net (code "102") (name "/SD4Data4") (class "Default")
      (node (ref "SD4") (pin "4") (pinfunction "4_4") (pintype "passive"))
    )
    (net (code "103") (name "/SD4Data5") (class "Default")
      (node (ref "SD4") (pin "2") (pinfunction "2_2") (pintype "passive"))
    )
    (net (code "104") (name "/SD4Data6") (class "Default")
      (node (ref "SD4") (pin "33") (pinfunction "33_33") (pintype "passive"))
    )
    (net (code "105") (name "/SD4Data7") (class "Default")
      (node (ref "SD4") (pin "31") (pinfunction "31_31") (pintype "passive"))
    )
    (net (code "106") (name "/SD4reset") (class "Default")
      (node (ref "R4") (pin "1") (pinfunction "1_1") (pintype "passive"))
      (node (ref "SD4") (pin "12") (pinfunction "12_12") (pintype "passive"))
    )
    (net (code "107") (name "/SD5Clk") (class "Default")
      (node (ref "SD5") (pin "8") (pinfunction "8_8") (pintype "passive"))
    )
    (net (code "108") (name "/SD5Cmd") (class "Default")
      (node (ref "SD5") (pin "25") (pinfunction "25_25") (pintype "passive"))
    )
    (net (code "109") (name "/SD5Data0") (class "Default")
      (node (ref "SD5") (pin "6") (pinfunction "6_6") (pintype "passive"))
    )
    (net (code "110") (name "/SD5Data1") (class "Default")
      (node (ref "SD5") (pin "29") (pinfunction "29_29") (pintype "passive"))
    )
    (net (code "111") (name "/SD5Data2") (class "Default")
      (node (ref "SD5") (pin "27") (pinfunction "27_27") (pintype "passive"))
    )
    (net (code "112") (name "/SD5Data3") (class "Default")
      (node (ref "SD5") (pin "10") (pinfunction "10_10") (pintype "passive"))
    )
    (net (code "113") (name "/SD5Data4") (class "Default")
      (node (ref "SD5") (pin "4") (pinfunction "4_4") (pintype "passive"))
    )
    (net (code "114") (name "/SD5Data5") (class "Default")
      (node (ref "SD5") (pin "2") (pinfunction "2_2") (pintype "passive"))
    )
    (net (code "115") (name "/SD5Data6") (class "Default")
      (node (ref "SD5") (pin "33") (pinfunction "33_33") (pintype "passive"))
    )
    (net (code "116") (name "/SD5Data7") (class "Default")
      (node (ref "SD5") (pin "31") (pinfunction "31_31") (pintype "passive"))
    )
    (net (code "117") (name "/SD5reset") (class "Default")
      (node (ref "R5") (pin "1") (pinfunction "1_1") (pintype "passive"))
      (node (ref "SD5") (pin "12") (pinfunction "12_12") (pintype "passive"))
    )
    (net (code "118") (name "/SD6Clk") (class "Default")
      (node (ref "SD6") (pin "8") (pinfunction "8_8") (pintype "passive"))
    )
    (net (code "119") (name "/SD6Cmd") (class "Default")
      (node (ref "SD6") (pin "25") (pinfunction "25_25") (pintype "passive"))
    )
    (net (code "120") (name "/SD6Data0") (class "Default")
      (node (ref "SD6") (pin "6") (pinfunction "6_6") (pintype "passive"))
    )
    (net (code "121") (name "/SD6Data1") (class "Default")
      (node (ref "SD6") (pin "29") (pinfunction "29_29") (pintype "passive"))
    )
    (net (code "122") (name "/SD6Data2") (class "Default")
      (node (ref "SD6") (pin "27") (pinfunction "27_27") (pintype "passive"))
    )
    (net (code "123") (name "/SD6Data3") (class "Default")
      (node (ref "SD6") (pin "10") (pinfunction "10_10") (pintype "passive"))
    )
    (net (code "124") (name "/SD6Data4") (class "Default")
      (node (ref "SD6") (pin "4") (pinfunction "4_4") (pintype "passive"))
    )
    (net (code "125") (name "/SD6Data5") (class "Default")
      (node (ref "SD6") (pin "2") (pinfunction "2_2") (pintype "passive"))
    )
    (net (code "126") (name "/SD6Data6") (class "Default")
      (node (ref "SD6") (pin "33") (pinfunction "33_33") (pintype "passive"))
    )
    (net (code "127") (name "/SD6Data7") (class "Default")
      (node (ref "SD6") (pin "31") (pinfunction "31_31") (pintype "passive"))
    )
    (net (code "128") (name "/SD6reset") (class "Default")
      (node (ref "R6") (pin "1") (pinfunction "1_1") (pintype "passive"))
      (node (ref "SD6") (pin "12") (pinfunction "12_12") (pintype "passive"))
    )
    (net (code "129") (name "/SD7Clk") (class "Default")
      (node (ref "SD7") (pin "8") (pinfunction "8_8") (pintype "passive"))
    )
    (net (code "130") (name "/SD7Cmd") (class "Default")
      (node (ref "SD7") (pin "25") (pinfunction "25_25") (pintype "passive"))
    )
    (net (code "131") (name "/SD7Data0") (class "Default")
      (node (ref "SD7") (pin "6") (pinfunction "6_6") (pintype "passive"))
    )
    (net (code "132") (name "/SD7Data1") (class "Default")
      (node (ref "SD7") (pin "29") (pinfunction "29_29") (pintype "passive"))
    )
    (net (code "133") (name "/SD7Data2") (class "Default")
      (node (ref "SD7") (pin "27") (pinfunction "27_27") (pintype "passive"))
    )
    (net (code "134") (name "/SD7Data3") (class "Default")
      (node (ref "SD7") (pin "10") (pinfunction "10_10") (pintype "passive"))
    )
    (net (code "135") (name "/SD7Data4") (class "Default")
      (node (ref "SD7") (pin "4") (pinfunction "4_4") (pintype "passive"))
    )
    (net (code "136") (name "/SD7Data5") (class "Default")
      (node (ref "SD7") (pin "2") (pinfunction "2_2") (pintype "passive"))
    )
    (net (code "137") (name "/SD7Data6") (class "Default")
      (node (ref "SD7") (pin "33") (pinfunction "33_33") (pintype "passive"))
    )
    (net (code "138") (name "/SD7Data7") (class "Default")
      (node (ref "SD7") (pin "31") (pinfunction "31_31") (pintype "passive"))
    )
    (net (code "139") (name "/SD7reset") (class "Default")
      (node (ref "R7") (pin "1") (pinfunction "1_1") (pintype "passive"))
      (node (ref "SD7") (pin "12") (pinfunction "12_12") (pintype "passive"))
    )
    (net (code "140") (name "/SD8Clk") (class "Default")
      (node (ref "SD8") (pin "8") (pinfunction "8_8") (pintype "passive"))
    )
    (net (code "141") (name "/SD8Cmd") (class "Default")
      (node (ref "SD8") (pin "25") (pinfunction "25_25") (pintype "passive"))
    )
    (net (code "142") (name "/SD8Data0") (class "Default")
      (node (ref "SD8") (pin "6") (pinfunction "6_6") (pintype "passive"))
    )
    (net (code "143") (name "/SD8Data1") (class "Default")
      (node (ref "SD8") (pin "29") (pinfunction "29_29") (pintype "passive"))
    )
    (net (code "144") (name "/SD8Data2") (class "Default")
      (node (ref "SD8") (pin "27") (pinfunction "27_27") (pintype "passive"))
    )
    (net (code "145") (name "/SD8Data3") (class "Default")
      (node (ref "SD8") (pin "10") (pinfunction "10_10") (pintype "passive"))
    )
    (net (code "146") (name "/SD8Data4") (class "Default")
      (node (ref "SD8") (pin "4") (pinfunction "4_4") (pintype "passive"))
    )
    (net (code "147") (name "/SD8Data5") (class "Default")
      (node (ref "SD8") (pin "2") (pinfunction "2_2") (pintype "passive"))
    )
    (net (code "148") (name "/SD8Data6") (class "Default")
      (node (ref "SD8") (pin "33") (pinfunction "33_33") (pintype "passive"))
    )
    (net (code "149") (name "/SD8Data7") (class "Default")
      (node (ref "SD8") (pin "31") (pinfunction "31_31") (pintype "passive"))
    )
    (net (code "150") (name "/SD8reset") (class "Default")
      (node (ref "R8") (pin "1") (pinfunction "1_1") (pintype "passive"))
      (node (ref "SD8") (pin "12") (pinfunction "12_12") (pintype "passive"))
    )
    (net (code "151") (name "/SD9Clk") (class "Default")
      (node (ref "SD9") (pin "8") (pinfunction "8_8") (pintype "passive"))
    )
    (net (code "152") (name "/SD9Cmd") (class "Default")
      (node (ref "SD9") (pin "25") (pinfunction "25_25") (pintype "passive"))
    )
    (net (code "153") (name "/SD9Data0") (class "Default")
      (node (ref "SD9") (pin "6") (pinfunction "6_6") (pintype "passive"))
    )
    (net (code "154") (name "/SD9Data1") (class "Default")
      (node (ref "SD9") (pin "29") (pinfunction "29_29") (pintype "passive"))
    )
    (net (code "155") (name "/SD9Data2") (class "Default")
      (node (ref "SD9") (pin "27") (pinfunction "27_27") (pintype "passive"))
    )
    (net (code "156") (name "/SD9Data3") (class "Default")
      (node (ref "SD9") (pin "10") (pinfunction "10_10") (pintype "passive"))
    )
    (net (code "157") (name "/SD9Data4") (class "Default")
      (node (ref "SD9") (pin "4") (pinfunction "4_4") (pintype "passive"))
    )
    (net (code "158") (name "/SD9Data5") (class "Default")
      (node (ref "SD9") (pin "2") (pinfunction "2_2") (pintype "passive"))
    )
    (net (code "159") (name "/SD9Data6") (class "Default")
      (node (ref "SD9") (pin "33") (pinfunction "33_33") (pintype "passive"))
    )
    (net (code "160") (name "/SD9Data7") (class "Default")
      (node (ref "SD9") (pin "31") (pinfunction "31_31") (pintype "passive"))
    )
    (net (code "161") (name "/SD9reset") (class "Default")
      (node (ref "R9") (pin "1") (pinfunction "1_1") (pintype "passive"))
      (node (ref "SD9") (pin "12") (pinfunction "12_12") (pintype "passive"))
    )
    (net (code "162") (name "/SD10Clk") (class "Default")
      (node (ref "SD10") (pin "8") (pinfunction "8_8") (pintype "passive"))
    )
    (net (code "163") (name "/SD10Cmd") (class "Default")
      (node (ref "SD10") (pin "25") (pinfunction "25_25") (pintype "passive"))
    )
    (net (code "164") (name "/SD10Data0") (class "Default")
      (node (ref "SD10") (pin "6") (pinfunction "6_6") (pintype "passive"))
    )
    (net (code "165") (name "/SD10Data1") (class "Default")
      (node (ref "SD10") (pin "29") (pinfunction "29_29") (pintype "passive"))
    )
    (net (code "166") (name "/SD10Data2") (class "Default")
      (node (ref "SD10") (pin "27") (pinfunction "27_27") (pintype "passive"))
    )
    (net (code "167") (name "/SD10Data3") (class "Default")
      (node (ref "SD10") (pin "10") (pinfunction "10_10") (pintype "passive"))
    )
    (net (code "168") (name "/SD10Data4") (class "Default")
      (node (ref "SD10") (pin "4") (pinfunction "4_4") (pintype "passive"))
    )
    (net (code "169") (name "/SD10Data5") (class "Default")
      (node (ref "SD10") (pin "2") (pinfunction "2_2") (pintype "passive"))
    )
    (net (code "170") (name "/SD10Data6") (class "Default")
      (node (ref "SD10") (pin "33") (pinfunction "33_33") (pintype "passive"))
    )
    (net (code "171") (name "/SD10Data7") (class "Default")
      (node (ref "SD10") (pin "31") (pinfunction "31_31") (pintype "passive"))
    )
    (net (code "172") (name "/SD10reset") (class "Default")
      (node (ref "R10") (pin "1") (pinfunction "1_1") (pintype "passive"))
      (node (ref "SD10") (pin "12") (pinfunction "12_12") (pintype "passive"))
    )
    (net (code "173") (name "/SD11Clk") (class "Default")
      (node (ref "SD11") (pin "8") (pinfunction "8_8") (pintype "passive"))
    )
    (net (code "174") (name "/SD11Cmd") (class "Default")
      (node (ref "SD11") (pin "25") (pinfunction "25_25") (pintype "passive"))
    )
    (net (code "175") (name "/SD11Data0") (class "Default")
      (node (ref "SD11") (pin "6") (pinfunction "6_6") (pintype "passive"))
    )
    (net (code "176") (name "/SD11Data1") (class "Default")
      (node (ref "SD11") (pin "29") (pinfunction "29_29") (pintype "passive"))
    )
    (net (code "177") (name "/SD11Data2") (class "Default")
      (node (ref "SD11") (pin "27") (pinfunction "27_27") (pintype "passive"))
    )
    (net (code "178") (name "/SD11Data3") (class "Default")
      (node (ref "SD11") (pin "10") (pinfunction "10_10") (pintype "passive"))
    )
    (net (code "179") (name "/SD11Data4") (class "Default")
      (node (ref "SD11") (pin "4") (pinfunction "4_4") (pintype "passive"))
    )
    (net (code "180") (name "/SD11Data5") (class "Default")
      (node (ref "SD11") (pin "2") (pinfunction "2_2") (pintype "passive"))
    )
    (net (code "181") (name "/SD11Data6") (class "Default")
      (node (ref "SD11") (pin "33") (pinfunction "33_33") (pintype "passive"))
    )
    (net (code "182") (name "/SD11Data7") (class "Default")
      (node (ref "SD11") (pin "31") (pinfunction "31_31") (pintype "passive"))
    )
    (net (code "183") (name "/SD11reset") (class "Default")
      (node (ref "R11") (pin "1") (pinfunction "1_1") (pintype "passive"))
      (node (ref "SD11") (pin "12") (pinfunction "12_12") (pintype "passive"))
    )
    (net (code "184") (name "/SD12Clk") (class "Default")
      (node (ref "SD12") (pin "8") (pinfunction "8_8") (pintype "passive"))
    )
    (net (code "185") (name "/SD12Cmd") (class "Default")
      (node (ref "SD12") (pin "25") (pinfunction "25_25") (pintype "passive"))
    )
    (net (code "186") (name "/SD12Data0") (class "Default")
      (node (ref "SD12") (pin "6") (pinfunction "6_6") (pintype "passive"))
    )
    (net (code "187") (name "/SD12Data1") (class "Default")
      (node (ref "SD12") (pin "29") (pinfunction "29_29") (pintype "passive"))
    )
    (net (code "188") (name "/SD12Data2") (class "Default")
      (node (ref "SD12") (pin "27") (pinfunction "27_27") (pintype "passive"))
    )
    (net (code "189") (name "/SD12Data3") (class "Default")
      (node (ref "SD12") (pin "10") (pinfunction "10_10") (pintype "passive"))
    )
    (net (code "190") (name "/SD12Data4") (class "Default")
      (node (ref "SD12") (pin "4") (pinfunction "4_4") (pintype "passive"))
    )
    (net (code "191") (name "/SD12Data5") (class "Default")
      (node (ref "SD12") (pin "2") (pinfunction "2_2") (pintype "passive"))
    )
    (net (code "192") (name "/SD12Data6") (class "Default")
      (node (ref "SD12") (pin "33") (pinfunction "33_33") (pintype "passive"))
    )
    (net (code "193") (name "/SD12Data7") (class "Default")
      (node (ref "SD12") (pin "31") (pinfunction "31_31") (pintype "passive"))
    )
    (net (code "194") (name "/SD12reset") (class "Default")
      (node (ref "R12") (pin "1") (pinfunction "1_1") (pintype "passive"))
      (node (ref "SD12") (pin "12") (pinfunction "12_12") (pintype "passive"))
    )
    (net (code "195") (name "/ZYNQ_TCK") (class "Default")
      (node (ref "P3") (pin "39") (pinfunction "39_39") (pintype "passive"))
      (node (ref "R95") (pin "1") (pinfunction "1_1") (pintype "passive"))
    )
    (net (code "196") (name "/ZYNQ_TDI") (class "Default")
      (node (ref "P3") (pin "38") (pinfunction "38_38") (pintype "passive"))
      (node (ref "R97") (pin "1") (pinfunction "1_1") (pintype "passive"))
    )
    (net (code "197") (name "/ZYNQ_TDO") (class "Default")
      (node (ref "P3") (pin "40") (pinfunction "40_40") (pintype "passive"))
      (node (ref "R96") (pin "1") (pinfunction "1_1") (pintype "passive"))
    )
    (net (code "198") (name "/ZYNQ_TMS") (class "Default")
      (node (ref "P3") (pin "37") (pinfunction "37_37") (pintype "passive"))
      (node (ref "R94") (pin "1") (pinfunction "1_1") (pintype "passive"))
    )
    (net (code "199") (name "1V8") (class "Default")
      (node (ref "JM1") (pin "1") (pinfunction "1_1") (pintype "passive"))
    )
    (net (code "200") (name "2V5") (class "Default")
      (node (ref "JM18") (pin "1") (pinfunction "1_1") (pintype "passive"))
    )
    (net (code "201") (name "3V3") (class "Default")
      (node (ref "C1") (pin "2") (pinfunction "2_2") (pintype "passive"))
      (node (ref "C10") (pin "2") (pinfunction "2_2") (pintype "passive"))
      (node (ref "C11") (pin "2") (pinfunction "2_2") (pintype "passive"))
      (node (ref "C12") (pin "2") (pinfunction "2_2") (pintype "passive"))
      (node (ref "C13") (pin "2") (pinfunction "2_2") (pintype "passive"))
      (node (ref "C14") (pin "2") (pinfunction "2_2") (pintype "passive"))
      (node (ref "C15") (pin "2") (pinfunction "2_2") (pintype "passive"))
      (node (ref "C16") (pin "2") (pinfunction "2_2") (pintype "passive"))
      (node (ref "C17") (pin "2") (pinfunction "2_2") (pintype "passive"))
      (node (ref "C18") (pin "2") (pinfunction "2_2") (pintype "passive"))
      (node (ref "C19") (pin "2") (pinfunction "2_2") (pintype "passive"))
      (node (ref "C2") (pin "2") (pinfunction "2_2") (pintype "passive"))
      (node (ref "C20") (pin "2") (pinfunction "2_2") (pintype "passive"))
      (node (ref "C21") (pin "2") (pinfunction "2_2") (pintype "passive"))
      (node (ref "C22") (pin "2") (pinfunction "2_2") (pintype "passive"))
      (node (ref "C23") (pin "2") (pinfunction "2_2") (pintype "passive"))
      (node (ref "C24") (pin "2") (pinfunction "2_2") (pintype "passive"))
      (node (ref "C3") (pin "2") (pinfunction "2_2") (pintype "passive"))
      (node (ref "C4") (pin "2") (pinfunction "2_2") (pintype "passive"))
      (node (ref "C5") (pin "2") (pinfunction "2_2") (pintype "passive"))
      (node (ref "C6") (pin "2") (pinfunction "2_2") (pintype "passive"))
      (node (ref "C7") (pin "2") (pinfunction "2_2") (pintype "passive"))
      (node (ref "C8") (pin "2") (pinfunction "2_2") (pintype "passive"))
      (node (ref "C9") (pin "2") (pinfunction "2_2") (pintype "passive"))
      (node (ref "JM1") (pin "3") (pinfunction "3_3") (pintype "passive"))
      (node (ref "JM18") (pin "3") (pinfunction "3_3") (pintype "passive"))
      (node (ref "R1") (pin "2") (pinfunction "2_2") (pintype "passive"))
      (node (ref "R10") (pin "2") (pinfunction "2_2") (pintype "passive"))
      (node (ref "R11") (pin "2") (pinfunction "2_2") (pintype "passive"))
      (node (ref "R12") (pin "2") (pinfunction "2_2") (pintype "passive"))
      (node (ref "R2") (pin "2") (pinfunction "2_2") (pintype "passive"))
      (node (ref "R3") (pin "2") (pinfunction "2_2") (pintype "passive"))
      (node (ref "R4") (pin "2") (pinfunction "2_2") (pintype "passive"))
      (node (ref "R5") (pin "2") (pinfunction "2_2") (pintype "passive"))
      (node (ref "R6") (pin "2") (pinfunction "2_2") (pintype "passive"))
      (node (ref "R7") (pin "2") (pinfunction "2_2") (pintype "passive"))
      (node (ref "R8") (pin "2") (pinfunction "2_2") (pintype "passive"))
      (node (ref "R9") (pin "2") (pinfunction "2_2") (pintype "passive"))
      (node (ref "SD1") (pin "20") (pinfunction "20_20") (pintype "passive"))
      (node (ref "SD1") (pin "21") (pinfunction "21_21") (pintype "passive"))
      (node (ref "SD1") (pin "22") (pinfunction "22_22") (pintype "passive"))
      (node (ref "SD1") (pin "23") (pinfunction "23_23") (pintype "passive"))
      (node (ref "SD10") (pin "20") (pinfunction "20_20") (pintype "passive"))
      (node (ref "SD10") (pin "21") (pinfunction "21_21") (pintype "passive"))
      (node (ref "SD10") (pin "22") (pinfunction "22_22") (pintype "passive"))
      (node (ref "SD10") (pin "23") (pinfunction "23_23") (pintype "passive"))
      (node (ref "SD11") (pin "20") (pinfunction "20_20") (pintype "passive"))
      (node (ref "SD11") (pin "21") (pinfunction "21_21") (pintype "passive"))
      (node (ref "SD11") (pin "22") (pinfunction "22_22") (pintype "passive"))
      (node (ref "SD11") (pin "23") (pinfunction "23_23") (pintype "passive"))
      (node (ref "SD12") (pin "20") (pinfunction "20_20") (pintype "passive"))
      (node (ref "SD12") (pin "21") (pinfunction "21_21") (pintype "passive"))
      (node (ref "SD12") (pin "22") (pinfunction "22_22") (pintype "passive"))
      (node (ref "SD12") (pin "23") (pinfunction "23_23") (pintype "passive"))
      (node (ref "SD2") (pin "20") (pinfunction "20_20") (pintype "passive"))
      (node (ref "SD2") (pin "21") (pinfunction "21_21") (pintype "passive"))
      (node (ref "SD2") (pin "22") (pinfunction "22_22") (pintype "passive"))
      (node (ref "SD2") (pin "23") (pinfunction "23_23") (pintype "passive"))
      (node (ref "SD3") (pin "20") (pinfunction "20_20") (pintype "passive"))
      (node (ref "SD3") (pin "21") (pinfunction "21_21") (pintype "passive"))
      (node (ref "SD3") (pin "22") (pinfunction "22_22") (pintype "passive"))
      (node (ref "SD3") (pin "23") (pinfunction "23_23") (pintype "passive"))
      (node (ref "SD4") (pin "20") (pinfunction "20_20") (pintype "passive"))
      (node (ref "SD4") (pin "21") (pinfunction "21_21") (pintype "passive"))
      (node (ref "SD4") (pin "22") (pinfunction "22_22") (pintype "passive"))
      (node (ref "SD4") (pin "23") (pinfunction "23_23") (pintype "passive"))
      (node (ref "SD5") (pin "20") (pinfunction "20_20") (pintype "passive"))
      (node (ref "SD5") (pin "21") (pinfunction "21_21") (pintype "passive"))
      (node (ref "SD5") (pin "22") (pinfunction "22_22") (pintype "passive"))
      (node (ref "SD5") (pin "23") (pinfunction "23_23") (pintype "passive"))
      (node (ref "SD6") (pin "20") (pinfunction "20_20") (pintype "passive"))
      (node (ref "SD6") (pin "21") (pinfunction "21_21") (pintype "passive"))
      (node (ref "SD6") (pin "22") (pinfunction "22_22") (pintype "passive"))
      (node (ref "SD6") (pin "23") (pinfunction "23_23") (pintype "passive"))
      (node (ref "SD7") (pin "20") (pinfunction "20_20") (pintype "passive"))
      (node (ref "SD7") (pin "21") (pinfunction "21_21") (pintype "passive"))
      (node (ref "SD7") (pin "22") (pinfunction "22_22") (pintype "passive"))
      (node (ref "SD7") (pin "23") (pinfunction "23_23") (pintype "passive"))
      (node (ref "SD8") (pin "20") (pinfunction "20_20") (pintype "passive"))
      (node (ref "SD8") (pin "21") (pinfunction "21_21") (pintype "passive"))
      (node (ref "SD8") (pin "22") (pinfunction "22_22") (pintype "passive"))
      (node (ref "SD8") (pin "23") (pinfunction "23_23") (pintype "passive"))
      (node (ref "SD9") (pin "20") (pinfunction "20_20") (pintype "passive"))
      (node (ref "SD9") (pin "21") (pinfunction "21_21") (pintype "passive"))
      (node (ref "SD9") (pin "22") (pinfunction "22_22") (pintype "passive"))
      (node (ref "SD9") (pin "23") (pinfunction "23_23") (pintype "passive"))
    )
    (net (code "202") (name "GND") (class "Default")
      (node (ref "C1") (pin "1") (pinfunction "1_1") (pintype "passive"))
      (node (ref "C10") (pin "1") (pinfunction "1_1") (pintype "passive"))
      (node (ref "C11") (pin "1") (pinfunction "1_1") (pintype "passive"))
      (node (ref "C12") (pin "1") (pinfunction "1_1") (pintype "passive"))
      (node (ref "C13") (pin "1") (pinfunction "1_1") (pintype "passive"))
      (node (ref "C14") (pin "1") (pinfunction "1_1") (pintype "passive"))
      (node (ref "C15") (pin "1") (pinfunction "1_1") (pintype "passive"))
      (node (ref "C16") (pin "1") (pinfunction "1_1") (pintype "passive"))
      (node (ref "C17") (pin "1") (pinfunction "1_1") (pintype "passive"))
      (node (ref "C18") (pin "1") (pinfunction "1_1") (pintype "passive"))
      (node (ref "C19") (pin "1") (pinfunction "1_1") (pintype "passive"))
      (node (ref "C2") (pin "1") (pinfunction "1_1") (pintype "passive"))
      (node (ref "C20") (pin "1") (pinfunction "1_1") (pintype "passive"))
      (node (ref "C21") (pin "1") (pinfunction "1_1") (pintype "passive"))
      (node (ref "C22") (pin "1") (pinfunction "1_1") (pintype "passive"))
      (node (ref "C23") (pin "1") (pinfunction "1_1") (pintype "passive"))
      (node (ref "C24") (pin "1") (pinfunction "1_1") (pintype "passive"))
      (node (ref "C3") (pin "1") (pinfunction "1_1") (pintype "passive"))
      (node (ref "C4") (pin "1") (pinfunction "1_1") (pintype "passive"))
      (node (ref "C5") (pin "1") (pinfunction "1_1") (pintype "passive"))
      (node (ref "C6") (pin "1") (pinfunction "1_1") (pintype "passive"))
      (node (ref "C7") (pin "1") (pinfunction "1_1") (pintype "passive"))
      (node (ref "C8") (pin "1") (pinfunction "1_1") (pintype "passive"))
      (node (ref "C9") (pin "1") (pinfunction "1_1") (pintype "passive"))
      (node (ref "P1") (pin "11") (pinfunction "11_11") (pintype "passive"))
      (node (ref "P1") (pin "12") (pinfunction "12_12") (pintype "passive"))
      (node (ref "P1") (pin "21") (pinfunction "21_21") (pintype "passive"))
      (node (ref "P1") (pin "22") (pinfunction "22_22") (pintype "passive"))
      (node (ref "P1") (pin "31") (pinfunction "31_31") (pintype "passive"))
      (node (ref "P1") (pin "32") (pinfunction "32_32") (pintype "passive"))
      (node (ref "P1") (pin "41") (pinfunction "41_41") (pintype "passive"))
      (node (ref "P1") (pin "42") (pinfunction "42_42") (pintype "passive"))
      (node (ref "P1") (pin "51") (pinfunction "51_51") (pintype "passive"))
      (node (ref "P1") (pin "52") (pinfunction "52_52") (pintype "passive"))
      (node (ref "P17") (pin "11") (pinfunction "11_11") (pintype "bidirectional"))
      (node (ref "P17") (pin "13") (pinfunction "13_13") (pintype "bidirectional"))
      (node (ref "P17") (pin "3") (pinfunction "3_3") (pintype "bidirectional"))
      (node (ref "P17") (pin "5") (pinfunction "5_5") (pintype "bidirectional"))
      (node (ref "P17") (pin "7") (pinfunction "7_7") (pintype "bidirectional"))
      (node (ref "P17") (pin "9") (pinfunction "9_9") (pintype "bidirectional"))
      (node (ref "P18") (pin "2") (pinfunction "2_2") (pintype "bidirectional"))
      (node (ref "P2") (pin "11") (pinfunction "11_11") (pintype "passive"))
      (node (ref "P2") (pin "12") (pinfunction "12_12") (pintype "passive"))
      (node (ref "P2") (pin "21") (pinfunction "21_21") (pintype "passive"))
      (node (ref "P2") (pin "22") (pinfunction "22_22") (pintype "passive"))
      (node (ref "P2") (pin "31") (pinfunction "31_31") (pintype "passive"))
      (node (ref "P2") (pin "32") (pinfunction "32_32") (pintype "passive"))
      (node (ref "P2") (pin "41") (pinfunction "41_41") (pintype "passive"))
      (node (ref "P2") (pin "42") (pinfunction "42_42") (pintype "passive"))
      (node (ref "P2") (pin "51") (pinfunction "51_51") (pintype "passive"))
      (node (ref "P2") (pin "52") (pinfunction "52_52") (pintype "passive"))
      (node (ref "P3") (pin "11") (pinfunction "11_11") (pintype "passive"))
      (node (ref "P3") (pin "12") (pinfunction "12_12") (pintype "passive"))
      (node (ref "P3") (pin "21") (pinfunction "21_21") (pintype "passive"))
      (node (ref "P3") (pin "22") (pinfunction "22_22") (pintype "passive"))
      (node (ref "P3") (pin "31") (pinfunction "31_31") (pintype "passive"))
      (node (ref "P3") (pin "32") (pinfunction "32_32") (pintype "passive"))
      (node (ref "P3") (pin "35") (pinfunction "35_35") (pintype "passive"))
      (node (ref "P3") (pin "36") (pinfunction "36_36") (pintype "passive"))
      (node (ref "P3") (pin "41") (pinfunction "41_41") (pintype "passive"))
      (node (ref "P3") (pin "42") (pinfunction "42_42") (pintype "passive"))
      (node (ref "P3") (pin "51") (pinfunction "51_51") (pintype "passive"))
      (node (ref "P3") (pin "52") (pinfunction "52_52") (pintype "passive"))
      (node (ref "P4") (pin "11") (pinfunction "11_11") (pintype "passive"))
      (node (ref "P4") (pin "12") (pinfunction "12_12") (pintype "passive"))
      (node (ref "P4") (pin "21") (pinfunction "21_21") (pintype "passive"))
      (node (ref "P4") (pin "22") (pinfunction "22_22") (pintype "passive"))
      (node (ref "P4") (pin "31") (pinfunction "31_31") (pintype "passive"))
      (node (ref "P4") (pin "32") (pinfunction "32_32") (pintype "passive"))
      (node (ref "P4") (pin "41") (pinfunction "41_41") (pintype "passive"))
      (node (ref "P4") (pin "42") (pinfunction "42_42") (pintype "passive"))
      (node (ref "P4") (pin "51") (pinfunction "51_51") (pintype "passive"))
      (node (ref "P4") (pin "52") (pinfunction "52_52") (pintype "passive"))
      (node (ref "P5") (pin "11") (pinfunction "11_11") (pintype "bidirectional"))
      (node (ref "P5") (pin "13") (pinfunction "13_13") (pintype "bidirectional"))
      (node (ref "P5") (pin "3") (pinfunction "3_3") (pintype "bidirectional"))
      (node (ref "P5") (pin "5") (pinfunction "5_5") (pintype "bidirectional"))
      (node (ref "P5") (pin "7") (pinfunction "7_7") (pintype "bidirectional"))
      (node (ref "P5") (pin "9") (pinfunction "9_9") (pintype "bidirectional"))
      (node (ref "SD1") (pin "1") (pinfunction "1_1") (pintype "passive"))
      (node (ref "SD1") (pin "11") (pinfunction "11_11") (pintype "passive"))
      (node (ref "SD1") (pin "13") (pinfunction "13_13") (pintype "passive"))
      (node (ref "SD1") (pin "14") (pinfunction "14_14") (pintype "passive"))
      (node (ref "SD1") (pin "16") (pinfunction "16_16") (pintype "passive"))
      (node (ref "SD1") (pin "17") (pinfunction "17_17") (pintype "passive"))
      (node (ref "SD1") (pin "18") (pinfunction "18_18") (pintype "passive"))
      (node (ref "SD1") (pin "19") (pinfunction "19_19") (pintype "passive"))
      (node (ref "SD1") (pin "24") (pinfunction "24_24") (pintype "passive"))
      (node (ref "SD1") (pin "26") (pinfunction "26_26") (pintype "passive"))
      (node (ref "SD1") (pin "28") (pinfunction "28_28") (pintype "passive"))
      (node (ref "SD1") (pin "3") (pinfunction "3_3") (pintype "passive"))
      (node (ref "SD1") (pin "30") (pinfunction "30_30") (pintype "passive"))
      (node (ref "SD1") (pin "32") (pinfunction "32_32") (pintype "passive"))
      (node (ref "SD1") (pin "34") (pinfunction "34_34") (pintype "passive"))
      (node (ref "SD1") (pin "5") (pinfunction "5_5") (pintype "passive"))
      (node (ref "SD1") (pin "7") (pinfunction "7_7") (pintype "passive"))
      (node (ref "SD1") (pin "9") (pinfunction "9_9") (pintype "passive"))
      (node (ref "SD10") (pin "1") (pinfunction "1_1") (pintype "passive"))
      (node (ref "SD10") (pin "11") (pinfunction "11_11") (pintype "passive"))
      (node (ref "SD10") (pin "13") (pinfunction "13_13") (pintype "passive"))
      (node (ref "SD10") (pin "14") (pinfunction "14_14") (pintype "passive"))
      (node (ref "SD10") (pin "16") (pinfunction "16_16") (pintype "passive"))
      (node (ref "SD10") (pin "17") (pinfunction "17_17") (pintype "passive"))
      (node (ref "SD10") (pin "18") (pinfunction "18_18") (pintype "passive"))
      (node (ref "SD10") (pin "19") (pinfunction "19_19") (pintype "passive"))
      (node (ref "SD10") (pin "24") (pinfunction "24_24") (pintype "passive"))
      (node (ref "SD10") (pin "26") (pinfunction "26_26") (pintype "passive"))
      (node (ref "SD10") (pin "28") (pinfunction "28_28") (pintype "passive"))
      (node (ref "SD10") (pin "3") (pinfunction "3_3") (pintype "passive"))
      (node (ref "SD10") (pin "30") (pinfunction "30_30") (pintype "passive"))
      (node (ref "SD10") (pin "32") (pinfunction "32_32") (pintype "passive"))
      (node (ref "SD10") (pin "34") (pinfunction "34_34") (pintype "passive"))
      (node (ref "SD10") (pin "5") (pinfunction "5_5") (pintype "passive"))
      (node (ref "SD10") (pin "7") (pinfunction "7_7") (pintype "passive"))
      (node (ref "SD10") (pin "9") (pinfunction "9_9") (pintype "passive"))
      (node (ref "SD11") (pin "1") (pinfunction "1_1") (pintype "passive"))
      (node (ref "SD11") (pin "11") (pinfunction "11_11") (pintype "passive"))
      (node (ref "SD11") (pin "13") (pinfunction "13_13") (pintype "passive"))
      (node (ref "SD11") (pin "14") (pinfunction "14_14") (pintype "passive"))
      (node (ref "SD11") (pin "16") (pinfunction "16_16") (pintype "passive"))
      (node (ref "SD11") (pin "17") (pinfunction "17_17") (pintype "passive"))
      (node (ref "SD11") (pin "18") (pinfunction "18_18") (pintype "passive"))
      (node (ref "SD11") (pin "19") (pinfunction "19_19") (pintype "passive"))
      (node (ref "SD11") (pin "24") (pinfunction "24_24") (pintype "passive"))
      (node (ref "SD11") (pin "26") (pinfunction "26_26") (pintype "passive"))
      (node (ref "SD11") (pin "28") (pinfunction "28_28") (pintype "passive"))
      (node (ref "SD11") (pin "3") (pinfunction "3_3") (pintype "passive"))
      (node (ref "SD11") (pin "30") (pinfunction "30_30") (pintype "passive"))
      (node (ref "SD11") (pin "32") (pinfunction "32_32") (pintype "passive"))
      (node (ref "SD11") (pin "34") (pinfunction "34_34") (pintype "passive"))
      (node (ref "SD11") (pin "5") (pinfunction "5_5") (pintype "passive"))
      (node (ref "SD11") (pin "7") (pinfunction "7_7") (pintype "passive"))
      (node (ref "SD11") (pin "9") (pinfunction "9_9") (pintype "passive"))
      (node (ref "SD12") (pin "1") (pinfunction "1_1") (pintype "passive"))
      (node (ref "SD12") (pin "11") (pinfunction "11_11") (pintype "passive"))
      (node (ref "SD12") (pin "13") (pinfunction "13_13") (pintype "passive"))
      (node (ref "SD12") (pin "14") (pinfunction "14_14") (pintype "passive"))
      (node (ref "SD12") (pin "16") (pinfunction "16_16") (pintype "passive"))
      (node (ref "SD12") (pin "17") (pinfunction "17_17") (pintype "passive"))
      (node (ref "SD12") (pin "18") (pinfunction "18_18") (pintype "passive"))
      (node (ref "SD12") (pin "19") (pinfunction "19_19") (pintype "passive"))
      (node (ref "SD12") (pin "24") (pinfunction "24_24") (pintype "passive"))
      (node (ref "SD12") (pin "26") (pinfunction "26_26") (pintype "passive"))
      (node (ref "SD12") (pin "28") (pinfunction "28_28") (pintype "passive"))
      (node (ref "SD12") (pin "3") (pinfunction "3_3") (pintype "passive"))
      (node (ref "SD12") (pin "30") (pinfunction "30_30") (pintype "passive"))
      (node (ref "SD12") (pin "32") (pinfunction "32_32") (pintype "passive"))
      (node (ref "SD12") (pin "34") (pinfunction "34_34") (pintype "passive"))
      (node (ref "SD12") (pin "5") (pinfunction "5_5") (pintype "passive"))
      (node (ref "SD12") (pin "7") (pinfunction "7_7") (pintype "passive"))
      (node (ref "SD12") (pin "9") (pinfunction "9_9") (pintype "passive"))
      (node (ref "SD2") (pin "1") (pinfunction "1_1") (pintype "passive"))
      (node (ref "SD2") (pin "11") (pinfunction "11_11") (pintype "passive"))
      (node (ref "SD2") (pin "13") (pinfunction "13_13") (pintype "passive"))
      (node (ref "SD2") (pin "14") (pinfunction "14_14") (pintype "passive"))
      (node (ref "SD2") (pin "16") (pinfunction "16_16") (pintype "passive"))
      (node (ref "SD2") (pin "17") (pinfunction "17_17") (pintype "passive"))
      (node (ref "SD2") (pin "18") (pinfunction "18_18") (pintype "passive"))
      (node (ref "SD2") (pin "19") (pinfunction "19_19") (pintype "passive"))
      (node (ref "SD2") (pin "24") (pinfunction "24_24") (pintype "passive"))
      (node (ref "SD2") (pin "26") (pinfunction "26_26") (pintype "passive"))
      (node (ref "SD2") (pin "28") (pinfunction "28_28") (pintype "passive"))
      (node (ref "SD2") (pin "3") (pinfunction "3_3") (pintype "passive"))
      (node (ref "SD2") (pin "30") (pinfunction "30_30") (pintype "passive"))
      (node (ref "SD2") (pin "32") (pinfunction "32_32") (pintype "passive"))
      (node (ref "SD2") (pin "34") (pinfunction "34_34") (pintype "passive"))
      (node (ref "SD2") (pin "5") (pinfunction "5_5") (pintype "passive"))
      (node (ref "SD2") (pin "7") (pinfunction "7_7") (pintype "passive"))
      (node (ref "SD2") (pin "9") (pinfunction "9_9") (pintype "passive"))
      (node (ref "SD3") (pin "1") (pinfunction "1_1") (pintype "passive"))
      (node (ref "SD3") (pin "11") (pinfunction "11_11") (pintype "passive"))
      (node (ref "SD3") (pin "13") (pinfunction "13_13") (pintype "passive"))
      (node (ref "SD3") (pin "14") (pinfunction "14_14") (pintype "passive"))
      (node (ref "SD3") (pin "16") (pinfunction "16_16") (pintype "passive"))
      (node (ref "SD3") (pin "17") (pinfunction "17_17") (pintype "passive"))
      (node (ref "SD3") (pin "18") (pinfunction "18_18") (pintype "passive"))
      (node (ref "SD3") (pin "19") (pinfunction "19_19") (pintype "passive"))
      (node (ref "SD3") (pin "24") (pinfunction "24_24") (pintype "passive"))
      (node (ref "SD3") (pin "26") (pinfunction "26_26") (pintype "passive"))
      (node (ref "SD3") (pin "28") (pinfunction "28_28") (pintype "passive"))
      (node (ref "SD3") (pin "3") (pinfunction "3_3") (pintype "passive"))
      (node (ref "SD3") (pin "30") (pinfunction "30_30") (pintype "passive"))
      (node (ref "SD3") (pin "32") (pinfunction "32_32") (pintype "passive"))
      (node (ref "SD3") (pin "34") (pinfunction "34_34") (pintype "passive"))
      (node (ref "SD3") (pin "5") (pinfunction "5_5") (pintype "passive"))
      (node (ref "SD3") (pin "7") (pinfunction "7_7") (pintype "passive"))
      (node (ref "SD3") (pin "9") (pinfunction "9_9") (pintype "passive"))
      (node (ref "SD4") (pin "1") (pinfunction "1_1") (pintype "passive"))
      (node (ref "SD4") (pin "11") (pinfunction "11_11") (pintype "passive"))
      (node (ref "SD4") (pin "13") (pinfunction "13_13") (pintype "passive"))
      (node (ref "SD4") (pin "14") (pinfunction "14_14") (pintype "passive"))
      (node (ref "SD4") (pin "16") (pinfunction "16_16") (pintype "passive"))
      (node (ref "SD4") (pin "17") (pinfunction "17_17") (pintype "passive"))
      (node (ref "SD4") (pin "18") (pinfunction "18_18") (pintype "passive"))
      (node (ref "SD4") (pin "19") (pinfunction "19_19") (pintype "passive"))
      (node (ref "SD4") (pin "24") (pinfunction "24_24") (pintype "passive"))
      (node (ref "SD4") (pin "26") (pinfunction "26_26") (pintype "passive"))
      (node (ref "SD4") (pin "28") (pinfunction "28_28") (pintype "passive"))
      (node (ref "SD4") (pin "3") (pinfunction "3_3") (pintype "passive"))
      (node (ref "SD4") (pin "30") (pinfunction "30_30") (pintype "passive"))
      (node (ref "SD4") (pin "32") (pinfunction "32_32") (pintype "passive"))
      (node (ref "SD4") (pin "34") (pinfunction "34_34") (pintype "passive"))
      (node (ref "SD4") (pin "5") (pinfunction "5_5") (pintype "passive"))
      (node (ref "SD4") (pin "7") (pinfunction "7_7") (pintype "passive"))
      (node (ref "SD4") (pin "9") (pinfunction "9_9") (pintype "passive"))
      (node (ref "SD5") (pin "1") (pinfunction "1_1") (pintype "passive"))
      (node (ref "SD5") (pin "11") (pinfunction "11_11") (pintype "passive"))
      (node (ref "SD5") (pin "13") (pinfunction "13_13") (pintype "passive"))
      (node (ref "SD5") (pin "14") (pinfunction "14_14") (pintype "passive"))
      (node (ref "SD5") (pin "16") (pinfunction "16_16") (pintype "passive"))
      (node (ref "SD5") (pin "17") (pinfunction "17_17") (pintype "passive"))
      (node (ref "SD5") (pin "18") (pinfunction "18_18") (pintype "passive"))
      (node (ref "SD5") (pin "19") (pinfunction "19_19") (pintype "passive"))
      (node (ref "SD5") (pin "24") (pinfunction "24_24") (pintype "passive"))
      (node (ref "SD5") (pin "26") (pinfunction "26_26") (pintype "passive"))
      (node (ref "SD5") (pin "28") (pinfunction "28_28") (pintype "passive"))
      (node (ref "SD5") (pin "3") (pinfunction "3_3") (pintype "passive"))
      (node (ref "SD5") (pin "30") (pinfunction "30_30") (pintype "passive"))
      (node (ref "SD5") (pin "32") (pinfunction "32_32") (pintype "passive"))
      (node (ref "SD5") (pin "34") (pinfunction "34_34") (pintype "passive"))
      (node (ref "SD5") (pin "5") (pinfunction "5_5") (pintype "passive"))
      (node (ref "SD5") (pin "7") (pinfunction "7_7") (pintype "passive"))
      (node (ref "SD5") (pin "9") (pinfunction "9_9") (pintype "passive"))
      (node (ref "SD6") (pin "1") (pinfunction "1_1") (pintype "passive"))
      (node (ref "SD6") (pin "11") (pinfunction "11_11") (pintype "passive"))
      (node (ref "SD6") (pin "13") (pinfunction "13_13") (pintype "passive"))
      (node (ref "SD6") (pin "14") (pinfunction "14_14") (pintype "passive"))
      (node (ref "SD6") (pin "16") (pinfunction "16_16") (pintype "passive"))
      (node (ref "SD6") (pin "17") (pinfunction "17_17") (pintype "passive"))
      (node (ref "SD6") (pin "18") (pinfunction "18_18") (pintype "passive"))
      (node (ref "SD6") (pin "19") (pinfunction "19_19") (pintype "passive"))
      (node (ref "SD6") (pin "24") (pinfunction "24_24") (pintype "passive"))
      (node (ref "SD6") (pin "26") (pinfunction "26_26") (pintype "passive"))
      (node (ref "SD6") (pin "28") (pinfunction "28_28") (pintype "passive"))
      (node (ref "SD6") (pin "3") (pinfunction "3_3") (pintype "passive"))
      (node (ref "SD6") (pin "30") (pinfunction "30_30") (pintype "passive"))
      (node (ref "SD6") (pin "32") (pinfunction "32_32") (pintype "passive"))
      (node (ref "SD6") (pin "34") (pinfunction "34_34") (pintype "passive"))
      (node (ref "SD6") (pin "5") (pinfunction "5_5") (pintype "passive"))
      (node (ref "SD6") (pin "7") (pinfunction "7_7") (pintype "passive"))
      (node (ref "SD6") (pin "9") (pinfunction "9_9") (pintype "passive"))
      (node (ref "SD7") (pin "1") (pinfunction "1_1") (pintype "passive"))
      (node (ref "SD7") (pin "11") (pinfunction "11_11") (pintype "passive"))
      (node (ref "SD7") (pin "13") (pinfunction "13_13") (pintype "passive"))
      (node (ref "SD7") (pin "14") (pinfunction "14_14") (pintype "passive"))
      (node (ref "SD7") (pin "16") (pinfunction "16_16") (pintype "passive"))
      (node (ref "SD7") (pin "17") (pinfunction "17_17") (pintype "passive"))
      (node (ref "SD7") (pin "18") (pinfunction "18_18") (pintype "passive"))
      (node (ref "SD7") (pin "19") (pinfunction "19_19") (pintype "passive"))
      (node (ref "SD7") (pin "24") (pinfunction "24_24") (pintype "passive"))
      (node (ref "SD7") (pin "26") (pinfunction "26_26") (pintype "passive"))
      (node (ref "SD7") (pin "28") (pinfunction "28_28") (pintype "passive"))
      (node (ref "SD7") (pin "3") (pinfunction "3_3") (pintype "passive"))
      (node (ref "SD7") (pin "30") (pinfunction "30_30") (pintype "passive"))
      (node (ref "SD7") (pin "32") (pinfunction "32_32") (pintype "passive"))
      (node (ref "SD7") (pin "34") (pinfunction "34_34") (pintype "passive"))
      (node (ref "SD7") (pin "5") (pinfunction "5_5") (pintype "passive"))
      (node (ref "SD7") (pin "7") (pinfunction "7_7") (pintype "passive"))
      (node (ref "SD7") (pin "9") (pinfunction "9_9") (pintype "passive"))
      (node (ref "SD8") (pin "1") (pinfunction "1_1") (pintype "passive"))
      (node (ref "SD8") (pin "11") (pinfunction "11_11") (pintype "passive"))
      (node (ref "SD8") (pin "13") (pinfunction "13_13") (pintype "passive"))
      (node (ref "SD8") (pin "14") (pinfunction "14_14") (pintype "passive"))
      (node (ref "SD8") (pin "16") (pinfunction "16_16") (pintype "passive"))
      (node (ref "SD8") (pin "17") (pinfunction "17_17") (pintype "passive"))
      (node (ref "SD8") (pin "18") (pinfunction "18_18") (pintype "passive"))
      (node (ref "SD8") (pin "19") (pinfunction "19_19") (pintype "passive"))
      (node (ref "SD8") (pin "24") (pinfunction "24_24") (pintype "passive"))
      (node (ref "SD8") (pin "26") (pinfunction "26_26") (pintype "passive"))
      (node (ref "SD8") (pin "28") (pinfunction "28_28") (pintype "passive"))
      (node (ref "SD8") (pin "3") (pinfunction "3_3") (pintype "passive"))
      (node (ref "SD8") (pin "30") (pinfunction "30_30") (pintype "passive"))
      (node (ref "SD8") (pin "32") (pinfunction "32_32") (pintype "passive"))
      (node (ref "SD8") (pin "34") (pinfunction "34_34") (pintype "passive"))
      (node (ref "SD8") (pin "5") (pinfunction "5_5") (pintype "passive"))
      (node (ref "SD8") (pin "7") (pinfunction "7_7") (pintype "passive"))
      (node (ref "SD8") (pin "9") (pinfunction "9_9") (pintype "passive"))
      (node (ref "SD9") (pin "1") (pinfunction "1_1") (pintype "passive"))
      (node (ref "SD9") (pin "11") (pinfunction "11_11") (pintype "passive"))
      (node (ref "SD9") (pin "13") (pinfunction "13_13") (pintype "passive"))
      (node (ref "SD9") (pin "14") (pinfunction "14_14") (pintype "passive"))
      (node (ref "SD9") (pin "16") (pinfunction "16_16") (pintype "passive"))
      (node (ref "SD9") (pin "17") (pinfunction "17_17") (pintype "passive"))
      (node (ref "SD9") (pin "18") (pinfunction "18_18") (pintype "passive"))
      (node (ref "SD9") (pin "19") (pinfunction "19_19") (pintype "passive"))
      (node (ref "SD9") (pin "24") (pinfunction "24_24") (pintype "passive"))
      (node (ref "SD9") (pin "26") (pinfunction "26_26") (pintype "passive"))
      (node (ref "SD9") (pin "28") (pinfunction "28_28") (pintype "passive"))
      (node (ref "SD9") (pin "3") (pinfunction "3_3") (pintype "passive"))
      (node (ref "SD9") (pin "30") (pinfunction "30_30") (pintype "passive"))
      (node (ref "SD9") (pin "32") (pinfunction "32_32") (pintype "passive"))
      (node (ref "SD9") (pin "34") (pinfunction "34_34") (pintype "passive"))
      (node (ref "SD9") (pin "5") (pinfunction "5_5") (pintype "passive"))
      (node (ref "SD9") (pin "7") (pinfunction "7_7") (pintype "passive"))
      (node (ref "SD9") (pin "9") (pinfunction "9_9") (pintype "passive"))
      (node (ref "TP6") (pin "1") (pinfunction "1_1") (pintype "passive"))
    )
    (net (code "203") (name "Net-(JM1-Pad2)") (class "Default")
      (node (ref "JM1") (pin "2") (pinfunction "2_2") (pintype "passive"))
      (node (ref "P17") (pin "2") (pinfunction "2_2") (pintype "bidirectional"))
    )
    (net (code "204") (name "Net-(JM18-Pad2)") (class "Default")
      (node (ref "JM18") (pin "2") (pinfunction "2_2") (pintype "passive"))
      (node (ref "P5") (pin "2") (pinfunction "2_2") (pintype "bidirectional"))
    )
    (net (code "205") (name "Net-(P5-Pad4)") (class "Default")
      (node (ref "P5") (pin "4") (pinfunction "4_4") (pintype "bidirectional"))
      (node (ref "R94") (pin "2") (pinfunction "2_2") (pintype "passive"))
    )
    (net (code "206") (name "Net-(P5-Pad6)") (class "Default")
      (node (ref "P5") (pin "6") (pinfunction "6_6") (pintype "bidirectional"))
      (node (ref "R95") (pin "2") (pinfunction "2_2") (pintype "passive"))
    )
    (net (code "207") (name "Net-(P5-Pad8)") (class "Default")
      (node (ref "P5") (pin "8") (pinfunction "8_8") (pintype "bidirectional"))
      (node (ref "R96") (pin "2") (pinfunction "2_2") (pintype "passive"))
    )
    (net (code "208") (name "Net-(P5-Pad10)") (class "Default")
      (node (ref "P5") (pin "10") (pinfunction "10_10") (pintype "bidirectional"))
      (node (ref "R97") (pin "2") (pinfunction "2_2") (pintype "passive"))
    )
    (net (code "209") (name "Net-(P17-Pad4)") (class "Default")
      (node (ref "P17") (pin "4") (pinfunction "4_4") (pintype "bidirectional"))
      (node (ref "R34") (pin "2") (pinfunction "2_2") (pintype "passive"))
    )
    (net (code "210") (name "Net-(P17-Pad6)") (class "Default")
      (node (ref "P17") (pin "6") (pinfunction "6_6") (pintype "bidirectional"))
      (node (ref "R35") (pin "2") (pinfunction "2_2") (pintype "passive"))
    )
    (net (code "211") (name "Net-(P17-Pad8)") (class "Default")
      (node (ref "P17") (pin "8") (pinfunction "8_8") (pintype "bidirectional"))
      (node (ref "R36") (pin "2") (pinfunction "2_2") (pintype "passive"))
    )
    (net (code "212") (name "Net-(P17-Pad10)") (class "Default")
      (node (ref "P17") (pin "10") (pinfunction "10_10") (pintype "bidirectional"))
      (node (ref "R37") (pin "2") (pinfunction "2_2") (pintype "passive"))
    )
    (net (code "213") (name "VDDGPIO") (class "Default")
      (node (ref "P1") (pin "1") (pinfunction "1_1") (pintype "passive"))
      (node (ref "P1") (pin "2") (pinfunction "2_2") (pintype "passive"))
    )
    (net (code "214") (name "Vin") (class "Default")
      (node (ref "P18") (pin "1") (pinfunction "1_1") (pintype "bidirectional"))
      (node (ref "TP5") (pin "1") (pinfunction "1_1") (pintype "passive"))
    )
    (net (code "215") (name "unconnected-(P1-Pad58)") (class "Default")
      (node (ref "P1") (pin "58") (pinfunction "58_58") (pintype "passive"))
    )
    (net (code "216") (name "unconnected-(P1-Pad60)") (class "Default")
      (node (ref "P1") (pin "60") (pinfunction "60_60") (pintype "passive"))
    )
    (net (code "217") (name "unconnected-(P1-PadHOLE)") (class "Default")
      (node (ref "P1") (pin "HOLE") (pinfunction "HOLE_HOLE") (pintype "passive"))
    )
    (net (code "218") (name "unconnected-(P2-Pad1)") (class "Default")
      (node (ref "P2") (pin "1") (pinfunction "1_1") (pintype "passive"))
    )
    (net (code "219") (name "unconnected-(P2-Pad2)") (class "Default")
      (node (ref "P2") (pin "2") (pinfunction "2_2") (pintype "passive"))
    )
    (net (code "220") (name "unconnected-(P2-Pad3)") (class "Default")
      (node (ref "P2") (pin "3") (pinfunction "3_3") (pintype "passive"))
    )
    (net (code "221") (name "unconnected-(P2-Pad4)") (class "Default")
      (node (ref "P2") (pin "4") (pinfunction "4_4") (pintype "passive"))
    )
    (net (code "222") (name "unconnected-(P2-Pad5)") (class "Default")
      (node (ref "P2") (pin "5") (pinfunction "5_5") (pintype "passive"))
    )
    (net (code "223") (name "unconnected-(P2-Pad6)") (class "Default")
      (node (ref "P2") (pin "6") (pinfunction "6_6") (pintype "passive"))
    )
    (net (code "224") (name "unconnected-(P2-Pad7)") (class "Default")
      (node (ref "P2") (pin "7") (pinfunction "7_7") (pintype "passive"))
    )
    (net (code "225") (name "unconnected-(P2-Pad8)") (class "Default")
      (node (ref "P2") (pin "8") (pinfunction "8_8") (pintype "passive"))
    )
    (net (code "226") (name "unconnected-(P2-Pad9)") (class "Default")
      (node (ref "P2") (pin "9") (pinfunction "9_9") (pintype "passive"))
    )
    (net (code "227") (name "unconnected-(P2-Pad10)") (class "Default")
      (node (ref "P2") (pin "10") (pinfunction "10_10") (pintype "passive"))
    )
    (net (code "228") (name "unconnected-(P2-Pad13)") (class "Default")
      (node (ref "P2") (pin "13") (pinfunction "13_13") (pintype "passive"))
    )
    (net (code "229") (name "unconnected-(P2-Pad14)") (class "Default")
      (node (ref "P2") (pin "14") (pinfunction "14_14") (pintype "passive"))
    )
    (net (code "230") (name "unconnected-(P2-Pad15)") (class "Default")
      (node (ref "P2") (pin "15") (pinfunction "15_15") (pintype "passive"))
    )
    (net (code "231") (name "unconnected-(P2-Pad16)") (class "Default")
      (node (ref "P2") (pin "16") (pinfunction "16_16") (pintype "passive"))
    )
    (net (code "232") (name "unconnected-(P2-Pad17)") (class "Default")
      (node (ref "P2") (pin "17") (pinfunction "17_17") (pintype "passive"))
    )
    (net (code "233") (name "unconnected-(P2-Pad18)") (class "Default")
      (node (ref "P2") (pin "18") (pinfunction "18_18") (pintype "passive"))
    )
    (net (code "234") (name "unconnected-(P2-Pad19)") (class "Default")
      (node (ref "P2") (pin "19") (pinfunction "19_19") (pintype "passive"))
    )
    (net (code "235") (name "unconnected-(P2-Pad20)") (class "Default")
      (node (ref "P2") (pin "20") (pinfunction "20_20") (pintype "passive"))
    )
    (net (code "236") (name "unconnected-(P2-Pad23)") (class "Default")
      (node (ref "P2") (pin "23") (pinfunction "23_23") (pintype "passive"))
    )
    (net (code "237") (name "unconnected-(P2-Pad24)") (class "Default")
      (node (ref "P2") (pin "24") (pinfunction "24_24") (pintype "passive"))
    )
    (net (code "238") (name "unconnected-(P2-Pad25)") (class "Default")
      (node (ref "P2") (pin "25") (pinfunction "25_25") (pintype "passive"))
    )
    (net (code "239") (name "unconnected-(P2-Pad26)") (class "Default")
      (node (ref "P2") (pin "26") (pinfunction "26_26") (pintype "passive"))
    )
    (net (code "240") (name "unconnected-(P2-Pad27)") (class "Default")
      (node (ref "P2") (pin "27") (pinfunction "27_27") (pintype "passive"))
    )
    (net (code "241") (name "unconnected-(P2-Pad28)") (class "Default")
      (node (ref "P2") (pin "28") (pinfunction "28_28") (pintype "passive"))
    )
    (net (code "242") (name "unconnected-(P2-Pad29)") (class "Default")
      (node (ref "P2") (pin "29") (pinfunction "29_29") (pintype "passive"))
    )
    (net (code "243") (name "unconnected-(P2-Pad30)") (class "Default")
      (node (ref "P2") (pin "30") (pinfunction "30_30") (pintype "passive"))
    )
    (net (code "244") (name "unconnected-(P2-Pad33)") (class "Default")
      (node (ref "P2") (pin "33") (pinfunction "33_33") (pintype "passive"))
    )
    (net (code "245") (name "unconnected-(P2-Pad34)") (class "Default")
      (node (ref "P2") (pin "34") (pinfunction "34_34") (pintype "passive"))
    )
    (net (code "246") (name "unconnected-(P2-Pad35)") (class "Default")
      (node (ref "P2") (pin "35") (pinfunction "35_35") (pintype "passive"))
    )
    (net (code "247") (name "unconnected-(P2-Pad36)") (class "Default")
      (node (ref "P2") (pin "36") (pinfunction "36_36") (pintype "passive"))
    )
    (net (code "248") (name "unconnected-(P2-Pad37)") (class "Default")
      (node (ref "P2") (pin "37") (pinfunction "37_37") (pintype "passive"))
    )
    (net (code "249") (name "unconnected-(P2-Pad38)") (class "Default")
      (node (ref "P2") (pin "38") (pinfunction "38_38") (pintype "passive"))
    )
    (net (code "250") (name "unconnected-(P2-Pad39)") (class "Default")
      (node (ref "P2") (pin "39") (pinfunction "39_39") (pintype "passive"))
    )
    (net (code "251") (name "unconnected-(P2-Pad40)") (class "Default")
      (node (ref "P2") (pin "40") (pinfunction "40_40") (pintype "passive"))
    )
    (net (code "252") (name "unconnected-(P2-Pad43)") (class "Default")
      (node (ref "P2") (pin "43") (pinfunction "43_43") (pintype "passive"))
    )
    (net (code "253") (name "unconnected-(P2-Pad44)") (class "Default")
      (node (ref "P2") (pin "44") (pinfunction "44_44") (pintype "passive"))
    )
    (net (code "254") (name "unconnected-(P2-Pad45)") (class "Default")
      (node (ref "P2") (pin "45") (pinfunction "45_45") (pintype "passive"))
    )
    (net (code "255") (name "unconnected-(P2-Pad46)") (class "Default")
      (node (ref "P2") (pin "46") (pinfunction "46_46") (pintype "passive"))
    )
    (net (code "256") (name "unconnected-(P2-Pad47)") (class "Default")
      (node (ref "P2") (pin "47") (pinfunction "47_47") (pintype "passive"))
    )
    (net (code "257") (name "unconnected-(P2-Pad48)") (class "Default")
      (node (ref "P2") (pin "48") (pinfunction "48_48") (pintype "passive"))
    )
    (net (code "258") (name "unconnected-(P2-Pad49)") (class "Default")
      (node (ref "P2") (pin "49") (pinfunction "49_49") (pintype "passive"))
    )
    (net (code "259") (name "unconnected-(P2-Pad50)") (class "Default")
      (node (ref "P2") (pin "50") (pinfunction "50_50") (pintype "passive"))
    )
    (net (code "260") (name "unconnected-(P2-Pad53)") (class "Default")
      (node (ref "P2") (pin "53") (pinfunction "53_53") (pintype "passive"))
    )
    (net (code "261") (name "unconnected-(P2-Pad54)") (class "Default")
      (node (ref "P2") (pin "54") (pinfunction "54_54") (pintype "passive"))
    )
    (net (code "262") (name "unconnected-(P2-Pad55)") (class "Default")
      (node (ref "P2") (pin "55") (pinfunction "55_55") (pintype "passive"))
    )
    (net (code "263") (name "unconnected-(P2-Pad56)") (class "Default")
      (node (ref "P2") (pin "56") (pinfunction "56_56") (pintype "passive"))
    )
    (net (code "264") (name "unconnected-(P2-Pad57)") (class "Default")
      (node (ref "P2") (pin "57") (pinfunction "57_57") (pintype "passive"))
    )
    (net (code "265") (name "unconnected-(P2-Pad58)") (class "Default")
      (node (ref "P2") (pin "58") (pinfunction "58_58") (pintype "passive"))
    )
    (net (code "266") (name "unconnected-(P2-Pad59)") (class "Default")
      (node (ref "P2") (pin "59") (pinfunction "59_59") (pintype "passive"))
    )
    (net (code "267") (name "unconnected-(P2-Pad60)") (class "Default")
      (node (ref "P2") (pin "60") (pinfunction "60_60") (pintype "passive"))
    )
    (net (code "268") (name "unconnected-(P2-PadHOLE)") (class "Default")
      (node (ref "P2") (pin "HOLE") (pinfunction "HOLE_HOLE") (pintype "passive"))
    )
    (net (code "269") (name "unconnected-(P3-Pad1)") (class "Default")
      (node (ref "P3") (pin "1") (pinfunction "1_1") (pintype "passive"))
    )
    (net (code "270") (name "unconnected-(P3-Pad2)") (class "Default")
      (node (ref "P3") (pin "2") (pinfunction "2_2") (pintype "passive"))
    )
    (net (code "271") (name "unconnected-(P3-Pad3)") (class "Default")
      (node (ref "P3") (pin "3") (pinfunction "3_3") (pintype "passive"))
    )
    (net (code "272") (name "unconnected-(P3-Pad4)") (class "Default")
      (node (ref "P3") (pin "4") (pinfunction "4_4") (pintype "passive"))
    )
    (net (code "273") (name "unconnected-(P3-Pad5)") (class "Default")
      (node (ref "P3") (pin "5") (pinfunction "5_5") (pintype "passive"))
    )
    (net (code "274") (name "unconnected-(P3-Pad6)") (class "Default")
      (node (ref "P3") (pin "6") (pinfunction "6_6") (pintype "passive"))
    )
    (net (code "275") (name "unconnected-(P3-Pad7)") (class "Default")
      (node (ref "P3") (pin "7") (pinfunction "7_7") (pintype "passive"))
    )
    (net (code "276") (name "unconnected-(P3-Pad8)") (class "Default")
      (node (ref "P3") (pin "8") (pinfunction "8_8") (pintype "passive"))
    )
    (net (code "277") (name "unconnected-(P3-Pad9)") (class "Default")
      (node (ref "P3") (pin "9") (pinfunction "9_9") (pintype "passive"))
    )
    (net (code "278") (name "unconnected-(P3-Pad10)") (class "Default")
      (node (ref "P3") (pin "10") (pinfunction "10_10") (pintype "passive"))
    )
    (net (code "279") (name "unconnected-(P3-Pad13)") (class "Default")
      (node (ref "P3") (pin "13") (pinfunction "13_13") (pintype "passive"))
    )
    (net (code "280") (name "unconnected-(P3-Pad14)") (class "Default")
      (node (ref "P3") (pin "14") (pinfunction "14_14") (pintype "passive"))
    )
    (net (code "281") (name "unconnected-(P3-Pad15)") (class "Default")
      (node (ref "P3") (pin "15") (pinfunction "15_15") (pintype "passive"))
    )
    (net (code "282") (name "unconnected-(P3-Pad16)") (class "Default")
      (node (ref "P3") (pin "16") (pinfunction "16_16") (pintype "passive"))
    )
    (net (code "283") (name "unconnected-(P3-Pad17)") (class "Default")
      (node (ref "P3") (pin "17") (pinfunction "17_17") (pintype "passive"))
    )
    (net (code "284") (name "unconnected-(P3-Pad18)") (class "Default")
      (node (ref "P3") (pin "18") (pinfunction "18_18") (pintype "passive"))
    )
    (net (code "285") (name "unconnected-(P3-Pad19)") (class "Default")
      (node (ref "P3") (pin "19") (pinfunction "19_19") (pintype "passive"))
    )
    (net (code "286") (name "unconnected-(P3-Pad20)") (class "Default")
      (node (ref "P3") (pin "20") (pinfunction "20_20") (pintype "passive"))
    )
    (net (code "287") (name "unconnected-(P3-Pad23)") (class "Default")
      (node (ref "P3") (pin "23") (pinfunction "23_23") (pintype "passive"))
    )
    (net (code "288") (name "unconnected-(P3-Pad24)") (class "Default")
      (node (ref "P3") (pin "24") (pinfunction "24_24") (pintype "passive"))
    )
    (net (code "289") (name "unconnected-(P3-Pad25)") (class "Default")
      (node (ref "P3") (pin "25") (pinfunction "25_25") (pintype "passive"))
    )
    (net (code "290") (name "unconnected-(P3-Pad26)") (class "Default")
      (node (ref "P3") (pin "26") (pinfunction "26_26") (pintype "passive"))
    )
    (net (code "291") (name "unconnected-(P3-Pad27)") (class "Default")
      (node (ref "P3") (pin "27") (pinfunction "27_27") (pintype "passive"))
    )
    (net (code "292") (name "unconnected-(P3-Pad28)") (class "Default")
      (node (ref "P3") (pin "28") (pinfunction "28_28") (pintype "passive"))
    )
    (net (code "293") (name "unconnected-(P3-Pad29)") (class "Default")
      (node (ref "P3") (pin "29") (pinfunction "29_29") (pintype "passive"))
    )
    (net (code "294") (name "unconnected-(P3-Pad30)") (class "Default")
      (node (ref "P3") (pin "30") (pinfunction "30_30") (pintype "passive"))
    )
    (net (code "295") (name "unconnected-(P3-Pad33)") (class "Default")
      (node (ref "P3") (pin "33") (pinfunction "33_33") (pintype "passive"))
    )
    (net (code "296") (name "unconnected-(P3-Pad34)") (class "Default")
      (node (ref "P3") (pin "34") (pinfunction "34_34") (pintype "passive"))
    )
    (net (code "297") (name "unconnected-(P3-Pad43)") (class "Default")
      (node (ref "P3") (pin "43") (pinfunction "43_43") (pintype "passive"))
    )
    (net (code "298") (name "unconnected-(P3-Pad44)") (class "Default")
      (node (ref "P3") (pin "44") (pinfunction "44_44") (pintype "passive"))
    )
    (net (code "299") (name "unconnected-(P3-Pad45)") (class "Default")
      (node (ref "P3") (pin "45") (pinfunction "45_45") (pintype "passive"))
    )
    (net (code "300") (name "unconnected-(P3-Pad46)") (class "Default")
      (node (ref "P3") (pin "46") (pinfunction "46_46") (pintype "passive"))
    )
    (net (code "301") (name "unconnected-(P3-Pad47)") (class "Default")
      (node (ref "P3") (pin "47") (pinfunction "47_47") (pintype "passive"))
    )
    (net (code "302") (name "unconnected-(P3-Pad48)") (class "Default")
      (node (ref "P3") (pin "48") (pinfunction "48_48") (pintype "passive"))
    )
    (net (code "303") (name "unconnected-(P3-Pad49)") (class "Default")
      (node (ref "P3") (pin "49") (pinfunction "49_49") (pintype "passive"))
    )
    (net (code "304") (name "unconnected-(P3-Pad50)") (class "Default")
      (node (ref "P3") (pin "50") (pinfunction "50_50") (pintype "passive"))
    )
    (net (code "305") (name "unconnected-(P3-Pad53)") (class "Default")
      (node (ref "P3") (pin "53") (pinfunction "53_53") (pintype "passive"))
    )
    (net (code "306") (name "unconnected-(P3-Pad54)") (class "Default")
      (node (ref "P3") (pin "54") (pinfunction "54_54") (pintype "passive"))
    )
    (net (code "307") (name "unconnected-(P3-Pad55)") (class "Default")
      (node (ref "P3") (pin "55") (pinfunction "55_55") (pintype "passive"))
    )
    (net (code "308") (name "unconnected-(P3-Pad56)") (class "Default")
      (node (ref "P3") (pin "56") (pinfunction "56_56") (pintype "passive"))
    )
    (net (code "309") (name "unconnected-(P3-Pad57)") (class "Default")
      (node (ref "P3") (pin "57") (pinfunction "57_57") (pintype "passive"))
    )
    (net (code "310") (name "unconnected-(P3-Pad58)") (class "Default")
      (node (ref "P3") (pin "58") (pinfunction "58_58") (pintype "passive"))
    )
    (net (code "311") (name "unconnected-(P3-Pad59)") (class "Default")
      (node (ref "P3") (pin "59") (pinfunction "59_59") (pintype "passive"))
    )
    (net (code "312") (name "unconnected-(P3-Pad60)") (class "Default")
      (node (ref "P3") (pin "60") (pinfunction "60_60") (pintype "passive"))
    )
    (net (code "313") (name "unconnected-(P3-PadHOLE)") (class "Default")
      (node (ref "P3") (pin "HOLE") (pinfunction "HOLE_HOLE") (pintype "passive"))
    )
    (net (code "314") (name "unconnected-(P4-Pad1)") (class "Default")
      (node (ref "P4") (pin "1") (pinfunction "1_1") (pintype "passive"))
    )
    (net (code "315") (name "unconnected-(P4-Pad2)") (class "Default")
      (node (ref "P4") (pin "2") (pinfunction "2_2") (pintype "passive"))
    )
    (net (code "316") (name "unconnected-(P4-Pad3)") (class "Default")
      (node (ref "P4") (pin "3") (pinfunction "3_3") (pintype "passive"))
    )
    (net (code "317") (name "unconnected-(P4-Pad4)") (class "Default")
      (node (ref "P4") (pin "4") (pinfunction "4_4") (pintype "passive"))
    )
    (net (code "318") (name "unconnected-(P4-Pad5)") (class "Default")
      (node (ref "P4") (pin "5") (pinfunction "5_5") (pintype "passive"))
    )
    (net (code "319") (name "unconnected-(P4-Pad6)") (class "Default")
      (node (ref "P4") (pin "6") (pinfunction "6_6") (pintype "passive"))
    )
    (net (code "320") (name "unconnected-(P4-Pad7)") (class "Default")
      (node (ref "P4") (pin "7") (pinfunction "7_7") (pintype "passive"))
    )
    (net (code "321") (name "unconnected-(P4-Pad8)") (class "Default")
      (node (ref "P4") (pin "8") (pinfunction "8_8") (pintype "passive"))
    )
    (net (code "322") (name "unconnected-(P4-Pad9)") (class "Default")
      (node (ref "P4") (pin "9") (pinfunction "9_9") (pintype "passive"))
    )
    (net (code "323") (name "unconnected-(P4-Pad10)") (class "Default")
      (node (ref "P4") (pin "10") (pinfunction "10_10") (pintype "passive"))
    )
    (net (code "324") (name "unconnected-(P4-Pad13)") (class "Default")
      (node (ref "P4") (pin "13") (pinfunction "13_13") (pintype "passive"))
    )
    (net (code "325") (name "unconnected-(P4-Pad14)") (class "Default")
      (node (ref "P4") (pin "14") (pinfunction "14_14") (pintype "passive"))
    )
    (net (code "326") (name "unconnected-(P4-Pad15)") (class "Default")
      (node (ref "P4") (pin "15") (pinfunction "15_15") (pintype "passive"))
    )
    (net (code "327") (name "unconnected-(P4-Pad16)") (class "Default")
      (node (ref "P4") (pin "16") (pinfunction "16_16") (pintype "passive"))
    )
    (net (code "328") (name "unconnected-(P4-Pad17)") (class "Default")
      (node (ref "P4") (pin "17") (pinfunction "17_17") (pintype "passive"))
    )
    (net (code "329") (name "unconnected-(P4-Pad18)") (class "Default")
      (node (ref "P4") (pin "18") (pinfunction "18_18") (pintype "passive"))
    )
    (net (code "330") (name "unconnected-(P4-Pad19)") (class "Default")
      (node (ref "P4") (pin "19") (pinfunction "19_19") (pintype "passive"))
    )
    (net (code "331") (name "unconnected-(P4-Pad20)") (class "Default")
      (node (ref "P4") (pin "20") (pinfunction "20_20") (pintype "passive"))
    )
    (net (code "332") (name "unconnected-(P4-Pad23)") (class "Default")
      (node (ref "P4") (pin "23") (pinfunction "23_23") (pintype "passive"))
    )
    (net (code "333") (name "unconnected-(P4-Pad24)") (class "Default")
      (node (ref "P4") (pin "24") (pinfunction "24_24") (pintype "passive"))
    )
    (net (code "334") (name "unconnected-(P4-Pad25)") (class "Default")
      (node (ref "P4") (pin "25") (pinfunction "25_25") (pintype "passive"))
    )
    (net (code "335") (name "unconnected-(P4-Pad26)") (class "Default")
      (node (ref "P4") (pin "26") (pinfunction "26_26") (pintype "passive"))
    )
    (net (code "336") (name "unconnected-(P4-Pad27)") (class "Default")
      (node (ref "P4") (pin "27") (pinfunction "27_27") (pintype "passive"))
    )
    (net (code "337") (name "unconnected-(P4-Pad28)") (class "Default")
      (node (ref "P4") (pin "28") (pinfunction "28_28") (pintype "passive"))
    )
    (net (code "338") (name "unconnected-(P4-Pad29)") (class "Default")
      (node (ref "P4") (pin "29") (pinfunction "29_29") (pintype "passive"))
    )
    (net (code "339") (name "unconnected-(P4-Pad30)") (class "Default")
      (node (ref "P4") (pin "30") (pinfunction "30_30") (pintype "passive"))
    )
    (net (code "340") (name "unconnected-(P4-Pad33)") (class "Default")
      (node (ref "P4") (pin "33") (pinfunction "33_33") (pintype "passive"))
    )
    (net (code "341") (name "unconnected-(P4-Pad34)") (class "Default")
      (node (ref "P4") (pin "34") (pinfunction "34_34") (pintype "passive"))
    )
    (net (code "342") (name "unconnected-(P4-Pad35)") (class "Default")
      (node (ref "P4") (pin "35") (pinfunction "35_35") (pintype "passive"))
    )
    (net (code "343") (name "unconnected-(P4-Pad36)") (class "Default")
      (node (ref "P4") (pin "36") (pinfunction "36_36") (pintype "passive"))
    )
    (net (code "344") (name "unconnected-(P4-Pad37)") (class "Default")
      (node (ref "P4") (pin "37") (pinfunction "37_37") (pintype "passive"))
    )
    (net (code "345") (name "unconnected-(P4-Pad38)") (class "Default")
      (node (ref "P4") (pin "38") (pinfunction "38_38") (pintype "passive"))
    )
    (net (code "346") (name "unconnected-(P4-Pad39)") (class "Default")
      (node (ref "P4") (pin "39") (pinfunction "39_39") (pintype "passive"))
    )
    (net (code "347") (name "unconnected-(P4-Pad40)") (class "Default")
      (node (ref "P4") (pin "40") (pinfunction "40_40") (pintype "passive"))
    )
    (net (code "348") (name "unconnected-(P4-Pad43)") (class "Default")
      (node (ref "P4") (pin "43") (pinfunction "43_43") (pintype "passive"))
    )
    (net (code "349") (name "unconnected-(P4-Pad44)") (class "Default")
      (node (ref "P4") (pin "44") (pinfunction "44_44") (pintype "passive"))
    )
    (net (code "350") (name "unconnected-(P4-Pad45)") (class "Default")
      (node (ref "P4") (pin "45") (pinfunction "45_45") (pintype "passive"))
    )
    (net (code "351") (name "unconnected-(P4-Pad46)") (class "Default")
      (node (ref "P4") (pin "46") (pinfunction "46_46") (pintype "passive"))
    )
    (net (code "352") (name "unconnected-(P4-Pad47)") (class "Default")
      (node (ref "P4") (pin "47") (pinfunction "47_47") (pintype "passive"))
    )
    (net (code "353") (name "unconnected-(P4-Pad48)") (class "Default")
      (node (ref "P4") (pin "48") (pinfunction "48_48") (pintype "passive"))
    )
    (net (code "354") (name "unconnected-(P4-Pad49)") (class "Default")
      (node (ref "P4") (pin "49") (pinfunction "49_49") (pintype "passive"))
    )
    (net (code "355") (name "unconnected-(P4-Pad50)") (class "Default")
      (node (ref "P4") (pin "50") (pinfunction "50_50") (pintype "passive"))
    )
    (net (code "356") (name "unconnected-(P4-Pad53)") (class "Default")
      (node (ref "P4") (pin "53") (pinfunction "53_53") (pintype "passive"))
    )
    (net (code "357") (name "unconnected-(P4-Pad54)") (class "Default")
      (node (ref "P4") (pin "54") (pinfunction "54_54") (pintype "passive"))
    )
    (net (code "358") (name "unconnected-(P4-Pad55)") (class "Default")
      (node (ref "P4") (pin "55") (pinfunction "55_55") (pintype "passive"))
    )
    (net (code "359") (name "unconnected-(P4-Pad56)") (class "Default")
      (node (ref "P4") (pin "56") (pinfunction "56_56") (pintype "passive"))
    )
    (net (code "360") (name "unconnected-(P4-Pad57)") (class "Default")
      (node (ref "P4") (pin "57") (pinfunction "57_57") (pintype "passive"))
    )
    (net (code "361") (name "unconnected-(P4-Pad58)") (class "Default")
      (node (ref "P4") (pin "58") (pinfunction "58_58") (pintype "passive"))
    )
    (net (code "362") (name "unconnected-(P4-Pad59)") (class "Default")
      (node (ref "P4") (pin "59") (pinfunction "59_59") (pintype "passive"))
    )
    (net (code "363") (name "unconnected-(P4-Pad60)") (class "Default")
      (node (ref "P4") (pin "60") (pinfunction "60_60") (pintype "passive"))
    )
    (net (code "364") (name "unconnected-(P4-PadHOLE)") (class "Default")
      (node (ref "P4") (pin "HOLE") (pinfunction "HOLE_HOLE") (pintype "passive"))
    )
    (net (code "365") (name "unconnected-(P5-Pad1)") (class "Default")
      (node (ref "P5") (pin "1") (pinfunction "1_1") (pintype "bidirectional+no_connect"))
    )
    (net (code "366") (name "unconnected-(P5-Pad12)") (class "Default")
      (node (ref "P5") (pin "12") (pinfunction "12_12") (pintype "bidirectional+no_connect"))
    )
    (net (code "367") (name "unconnected-(P5-Pad14)") (class "Default")
      (node (ref "P5") (pin "14") (pinfunction "14_14") (pintype "bidirectional+no_connect"))
    )
    (net (code "368") (name "unconnected-(P5-PadHOLE)") (class "Default")
      (node (ref "P5") (pin "HOLE") (pinfunction "HOLE_HOLE") (pintype "passive"))
    )
    (net (code "369") (name "unconnected-(P5-PadHOLE)_1") (class "Default")
      (node (ref "P5") (pin "HOLE") (pinfunction "HOLE_HOLE") (pintype "passive"))
    )
    (net (code "370") (name "unconnected-(P17-Pad1)") (class "Default")
      (node (ref "P17") (pin "1") (pinfunction "1_1") (pintype "bidirectional+no_connect"))
    )
    (net (code "371") (name "unconnected-(P17-Pad12)") (class "Default")
      (node (ref "P17") (pin "12") (pinfunction "12_12") (pintype "bidirectional+no_connect"))
    )
    (net (code "372") (name "unconnected-(P17-Pad14)") (class "Default")
      (node (ref "P17") (pin "14") (pinfunction "14_14") (pintype "bidirectional+no_connect"))
    )
    (net (code "373") (name "unconnected-(P17-PadHOLE)") (class "Default")
      (node (ref "P17") (pin "HOLE") (pinfunction "HOLE_HOLE") (pintype "passive"))
    )
    (net (code "374") (name "unconnected-(P17-PadHOLE)_1") (class "Default")
      (node (ref "P17") (pin "HOLE") (pinfunction "HOLE_HOLE") (pintype "passive"))
    )
  )
)
